# CanShark.net
KiCad netlist of a schematic drawn in EAGLE
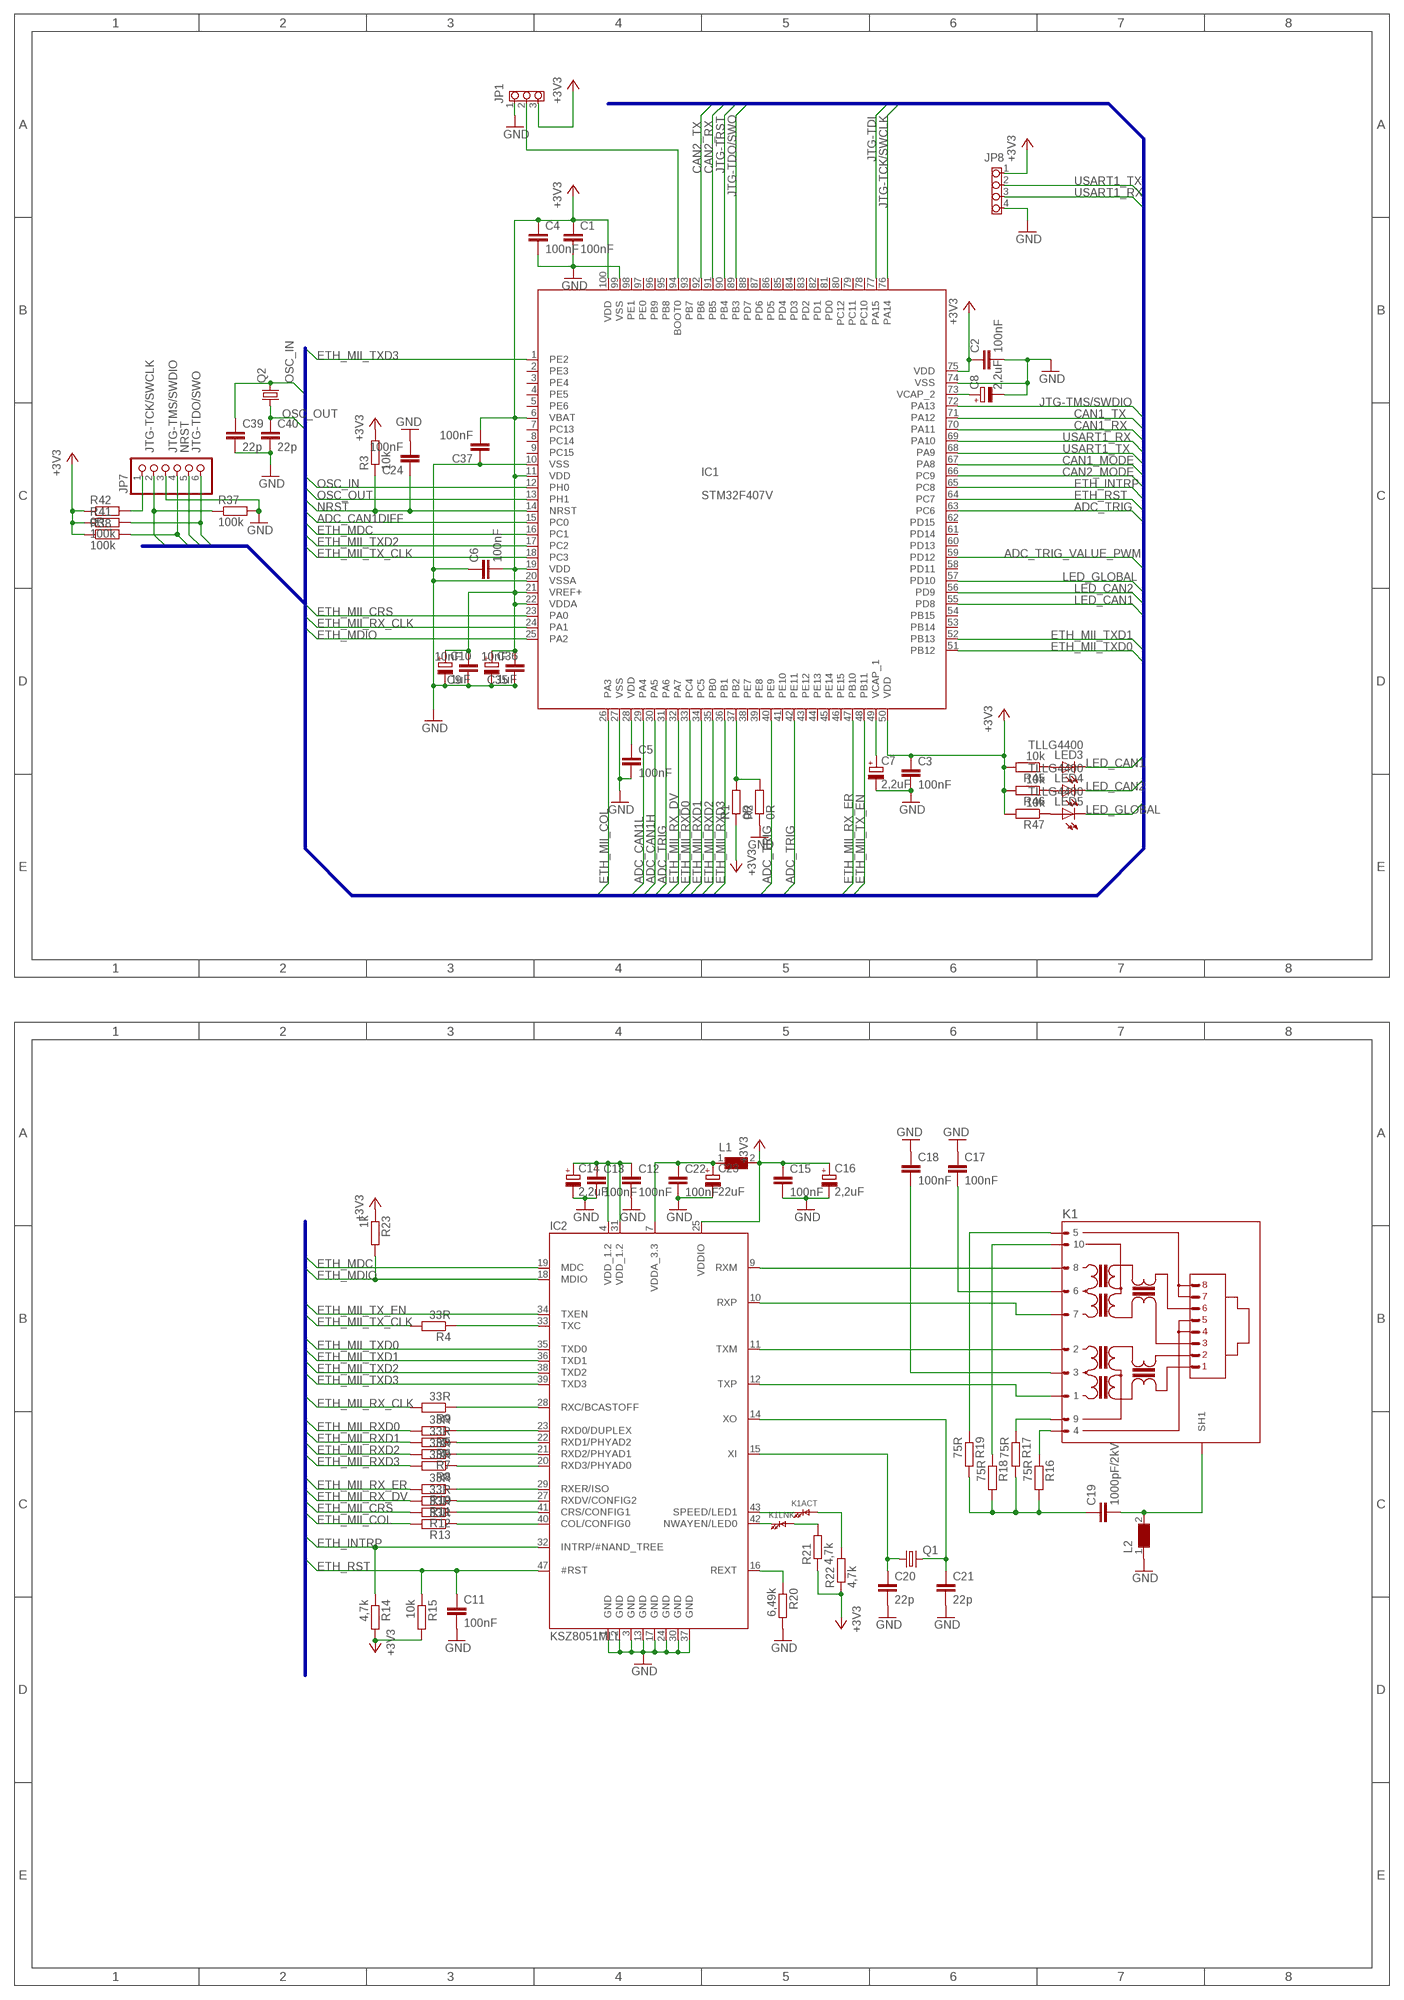
[diagram p0: schematic, sheet 1, part 1 of 3]
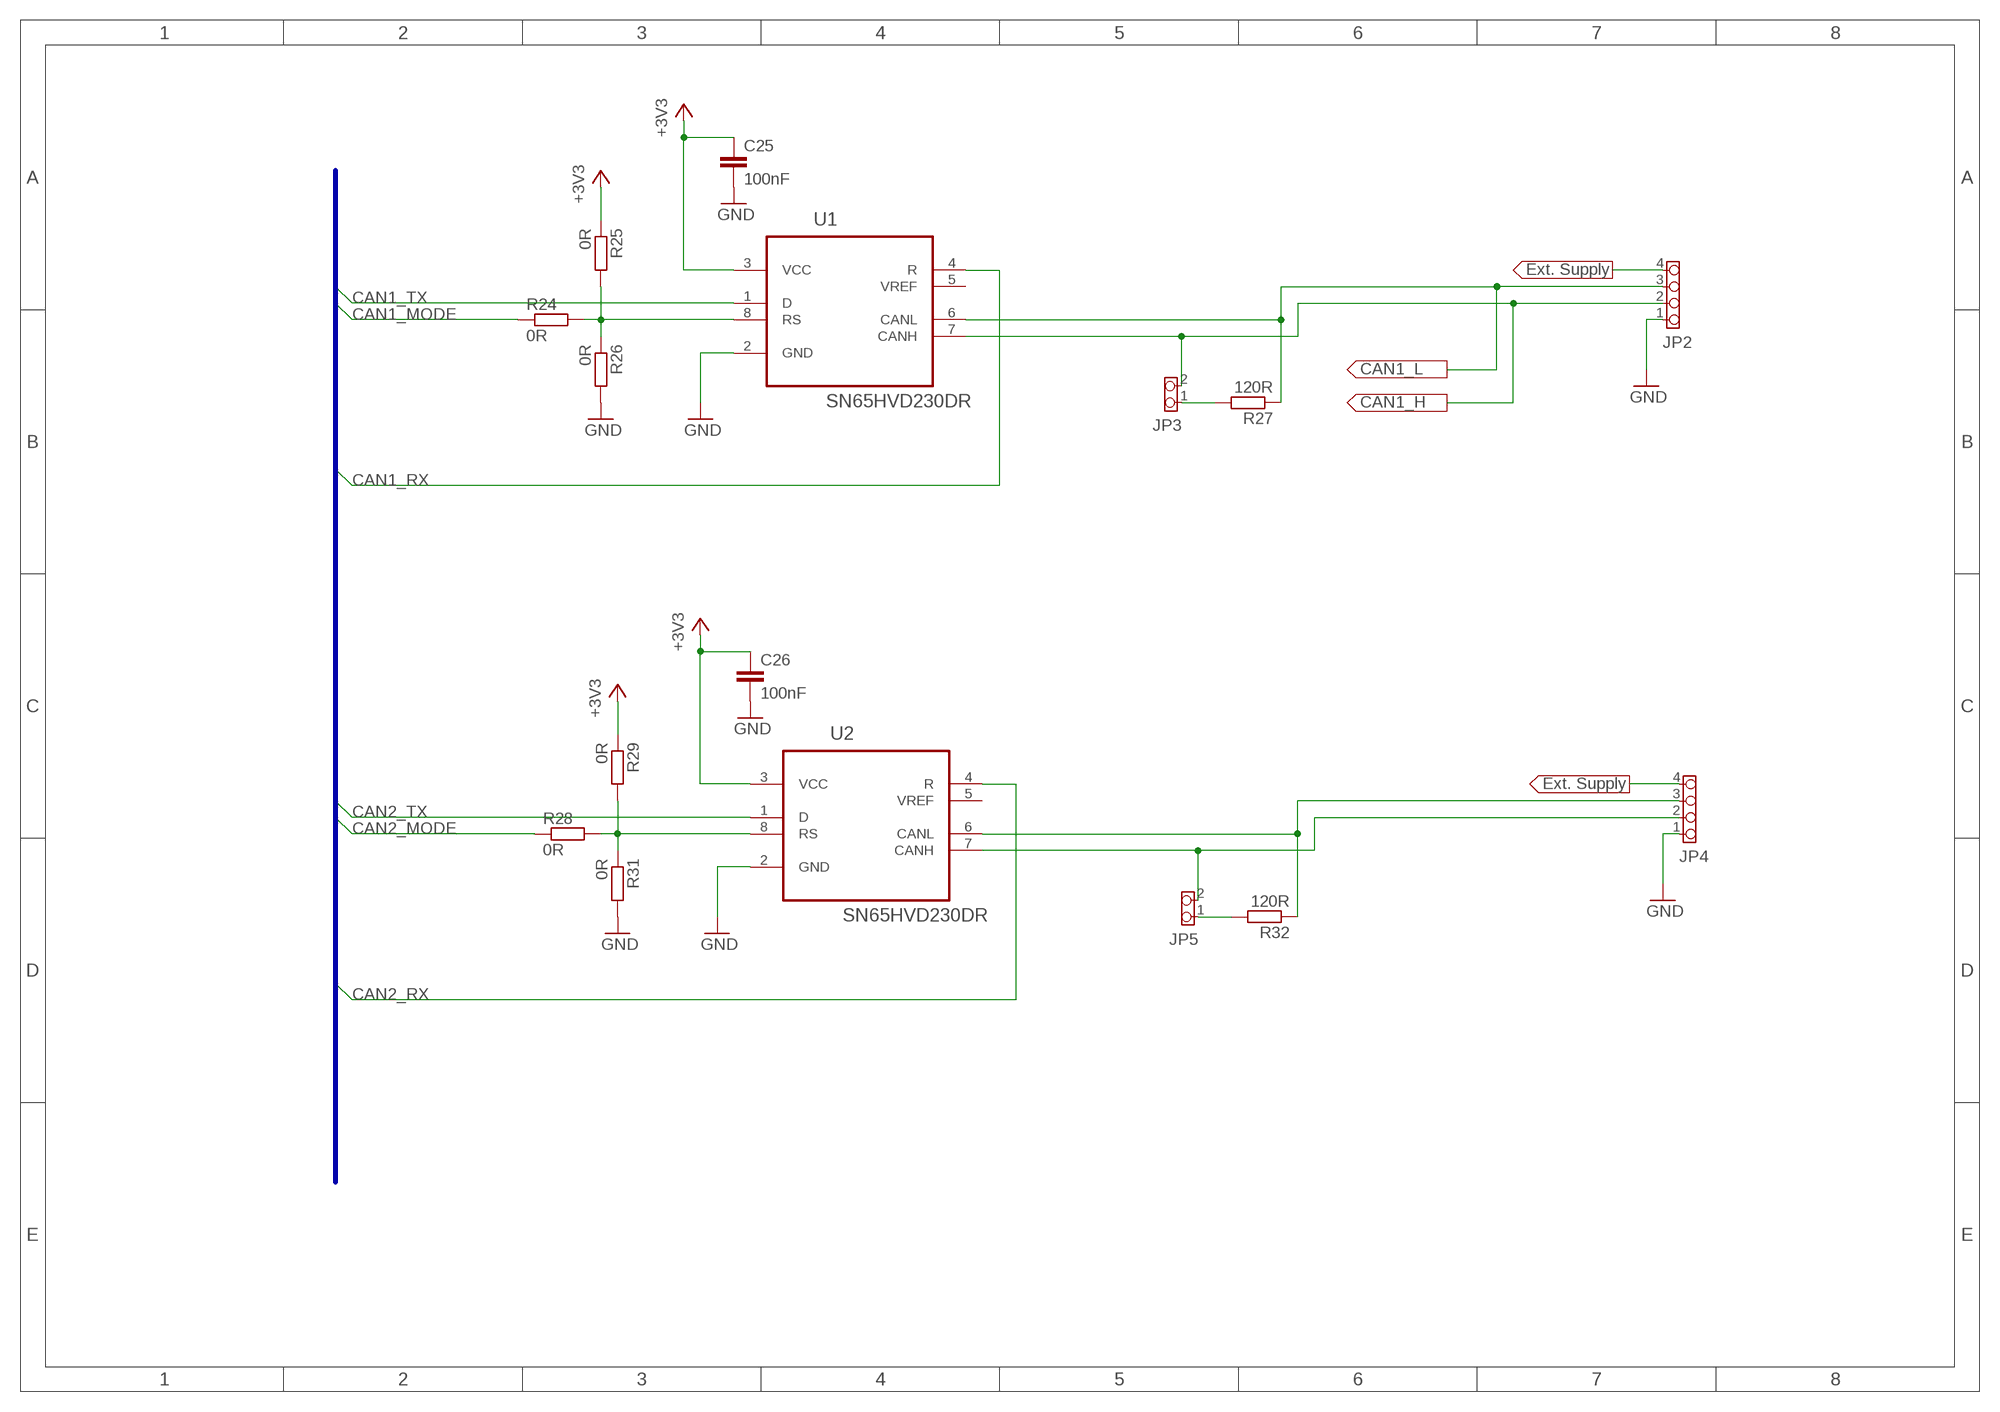
[diagram p1: schematic, sheet 1, part 2 of 3]
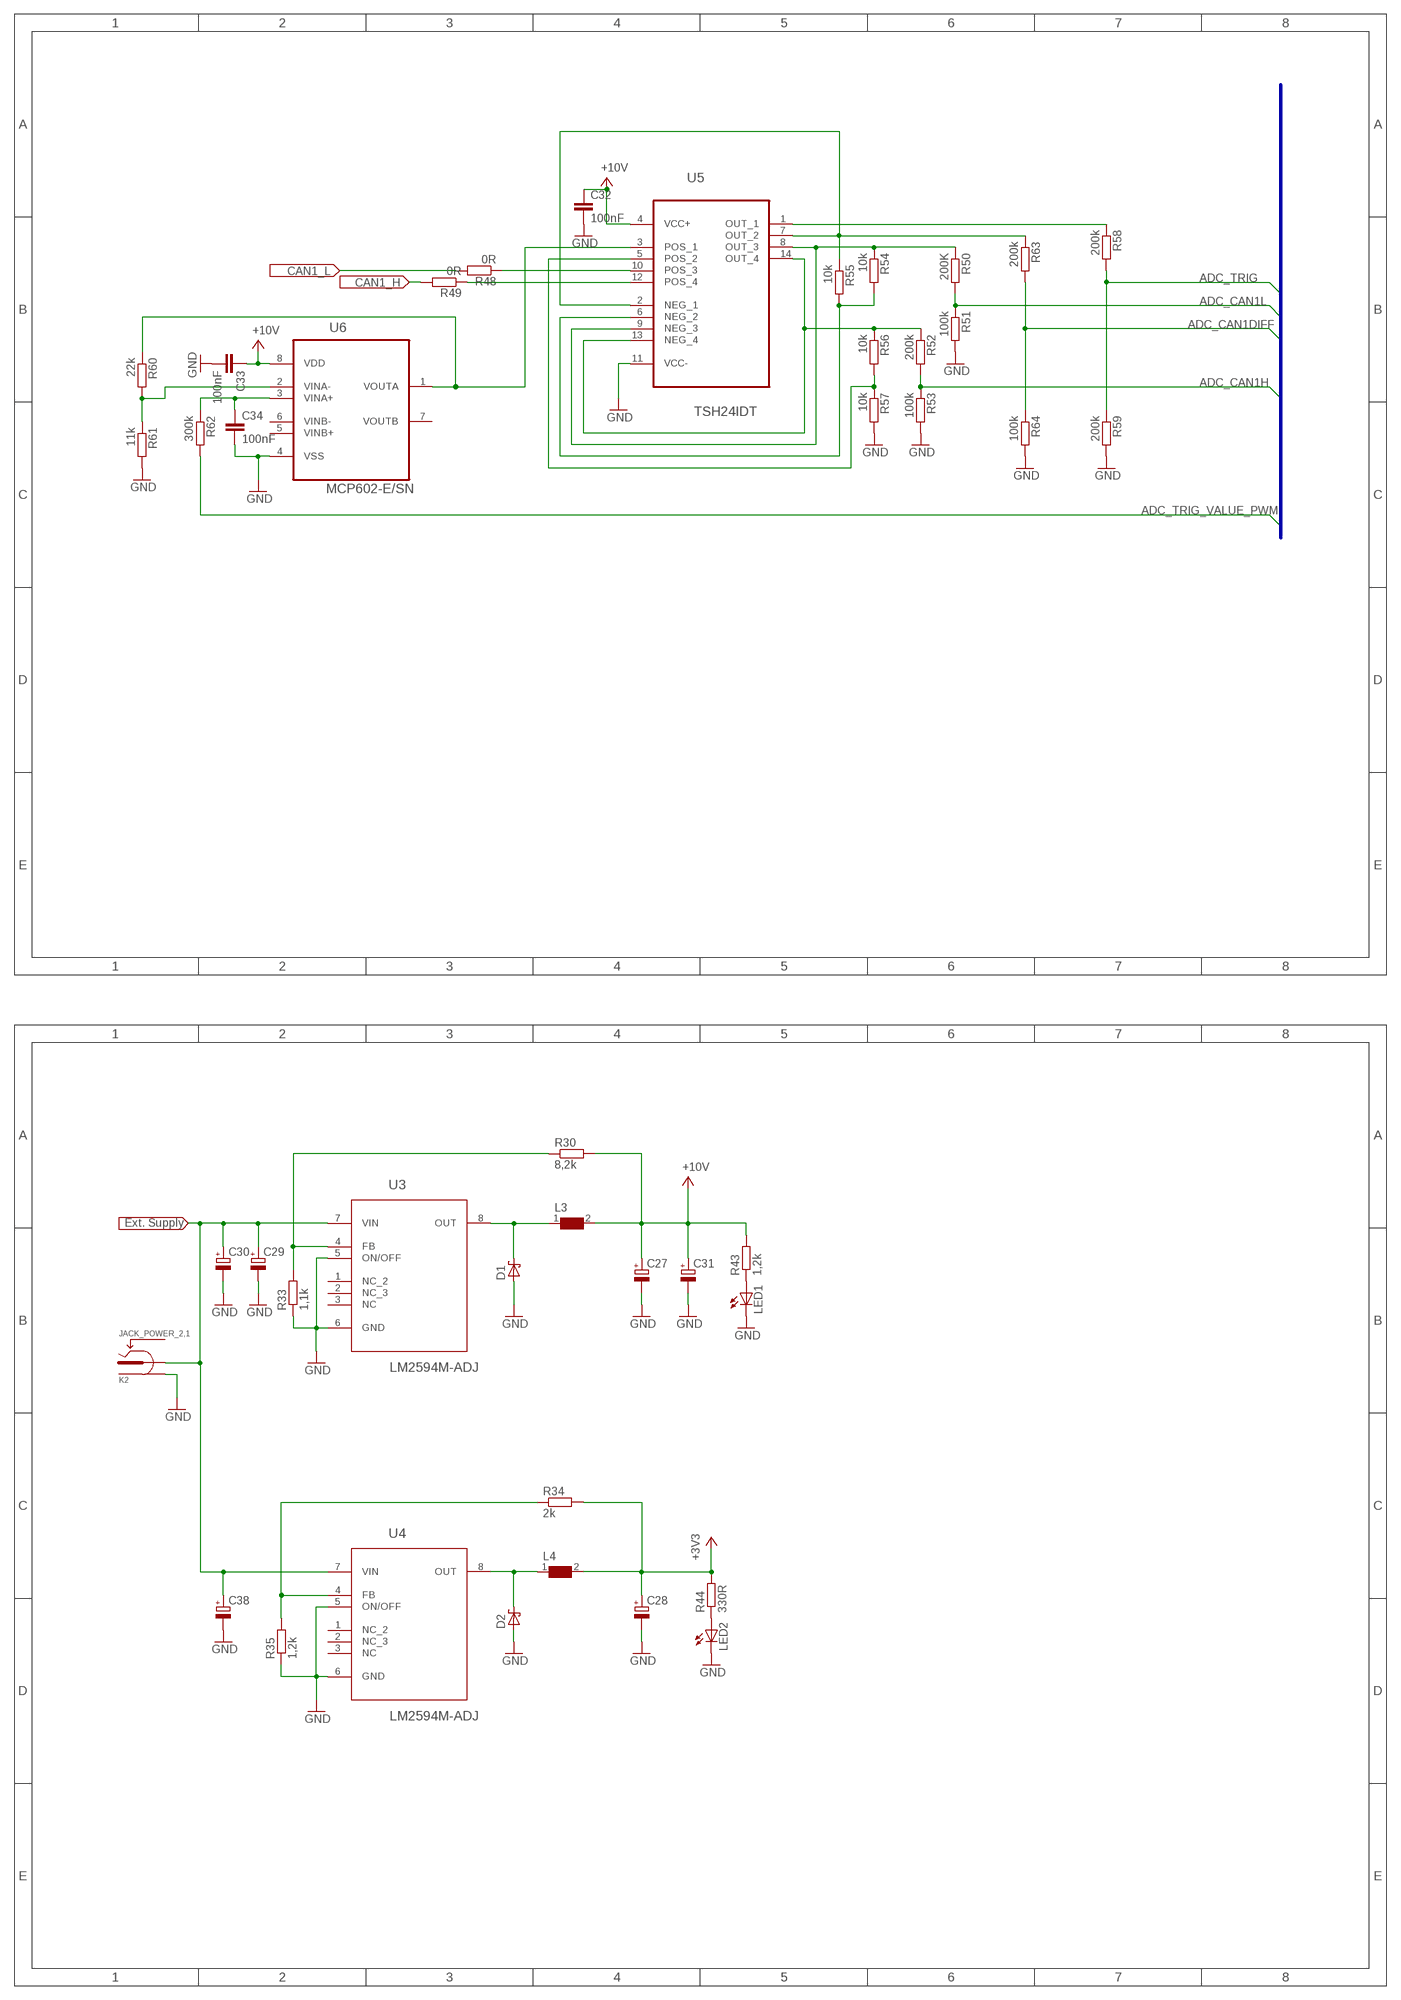
[diagram p2: schematic, sheet 1, part 3 of 3]

(export (version "E")
  (design (tool "Eeschema 10.0.6"))
  (components
    (comp (ref "C1")
      (value "100nF")
      (footprint "eagle-import:SMD0603")
      (libsource (lib "eagle-import") (part "KERAMICKYSMD0603"))
    )
    (comp (ref "C2")
      (value "100nF")
      (footprint "eagle-import:SMD0603")
      (libsource (lib "eagle-import") (part "KERAMICKYSMD0603"))
    )
    (comp (ref "C3")
      (value "100nF")
      (footprint "eagle-import:SMD0603")
      (libsource (lib "eagle-import") (part "KERAMICKYSMD0603"))
    )
    (comp (ref "C4")
      (value "100nF")
      (footprint "eagle-import:SMD0603")
      (libsource (lib "eagle-import") (part "KERAMICKYSMD0603"))
    )
    (comp (ref "C5")
      (value "100nF")
      (footprint "eagle-import:SMD0603")
      (libsource (lib "eagle-import") (part "KERAMICKYSMD0603"))
    )
    (comp (ref "C6")
      (value "100nF")
      (footprint "eagle-import:SMD0603")
      (libsource (lib "eagle-import") (part "KERAMICKYSMD0603"))
    )
    (comp (ref "C7")
      (value "2,2uF")
      (footprint "eagle-import:SMC_A")
      (libsource (lib "eagle-import") (part "CPOL-EUSMCA"))
    )
    (comp (ref "C8")
      (value "2,2uF")
      (footprint "eagle-import:SMC_A")
      (libsource (lib "eagle-import") (part "CPOL-EUSMCA"))
    )
    (comp (ref "C9")
      (value "10nF")
      (footprint "eagle-import:SMD0603")
      (libsource (lib "eagle-import") (part "KERAMICKYSMD0603"))
    )
    (comp (ref "C10")
      (value "1uF")
      (footprint "eagle-import:SMC_A")
      (libsource (lib "eagle-import") (part "CPOL-EUSMCA"))
    )
    (comp (ref "C11")
      (value "100nF")
      (footprint "eagle-import:SMD0603")
      (libsource (lib "eagle-import") (part "KERAMICKYSMD0603"))
    )
    (comp (ref "C12")
      (value "100nF")
      (footprint "eagle-import:SMD0603")
      (libsource (lib "eagle-import") (part "KERAMICKYSMD0603"))
    )
    (comp (ref "C13")
      (value "100nF")
      (footprint "eagle-import:SMD0603")
      (libsource (lib "eagle-import") (part "KERAMICKYSMD0603"))
    )
    (comp (ref "C14")
      (value "2,2uF")
      (footprint "eagle-import:SMC_A")
      (libsource (lib "eagle-import") (part "CPOL-EUSMCA"))
    )
    (comp (ref "C15")
      (value "100nF")
      (footprint "eagle-import:SMD0603")
      (libsource (lib "eagle-import") (part "KERAMICKYSMD0603"))
    )
    (comp (ref "C16")
      (value "2,2uF")
      (footprint "eagle-import:SMC_A")
      (libsource (lib "eagle-import") (part "CPOL-EUSMCA"))
    )
    (comp (ref "C17")
      (value "100nF")
      (footprint "eagle-import:SMD0603")
      (libsource (lib "eagle-import") (part "KERAMICKYSMD0603"))
    )
    (comp (ref "C18")
      (value "100nF")
      (footprint "eagle-import:SMD0603")
      (libsource (lib "eagle-import") (part "KERAMICKYSMD0603"))
    )
    (comp (ref "C19")
      (value "1000pF/2kV")
      (footprint "eagle-import:SMD1206")
      (libsource (lib "eagle-import") (part "KERAMICKYSMD1206"))
    )
    (comp (ref "C20")
      (value "22p")
      (footprint "eagle-import:SMD0603")
      (libsource (lib "eagle-import") (part "KERAMICKYSMD0603"))
    )
    (comp (ref "C21")
      (value "22p")
      (footprint "eagle-import:SMD0603")
      (libsource (lib "eagle-import") (part "KERAMICKYSMD0603"))
    )
    (comp (ref "C22")
      (value "100nF")
      (footprint "eagle-import:SMD0603")
      (libsource (lib "eagle-import") (part "KERAMICKYSMD0603"))
    )
    (comp (ref "C23")
      (value "22uF")
      (footprint "eagle-import:SMC_A")
      (libsource (lib "eagle-import") (part "CPOL-EUSMCA"))
    )
    (comp (ref "C24")
      (value "100nF")
      (footprint "eagle-import:SMD0603")
      (libsource (lib "eagle-import") (part "KERAMICKYSMD0603"))
    )
    (comp (ref "C25")
      (value "100nF")
      (footprint "eagle-import:SMD0603")
      (libsource (lib "eagle-import") (part "KERAMICKYSMD0603"))
    )
    (comp (ref "C26")
      (value "100nF")
      (footprint "eagle-import:SMD0603")
      (libsource (lib "eagle-import") (part "KERAMICKYSMD0603"))
    )
    (comp (ref "C27")
      (value "CPOL-EUC/6032-28R")
      (footprint "eagle-import:C_6032-28R")
      (libsource (lib "eagle-import") (part "CPOL-EUC/6032-28R"))
    )
    (comp (ref "C28")
      (value "CPOL-EUC/6032-28R")
      (footprint "eagle-import:C_6032-28R")
      (libsource (lib "eagle-import") (part "CPOL-EUC/6032-28R"))
    )
    (comp (ref "C29")
      (value "CPOL-EUC/6032-28R")
      (footprint "eagle-import:C_6032-28R")
      (libsource (lib "eagle-import") (part "CPOL-EUC/6032-28R"))
    )
    (comp (ref "C30")
      (value "CPOL-EUA/3216-18R")
      (footprint "eagle-import:A_3216-18R")
      (libsource (lib "eagle-import") (part "CPOL-EUA/3216-18R"))
    )
    (comp (ref "C31")
      (value "CPOL-EUA/3216-18R")
      (footprint "eagle-import:A_3216-18R")
      (libsource (lib "eagle-import") (part "CPOL-EUA/3216-18R"))
    )
    (comp (ref "C32")
      (value "100nF")
      (footprint "eagle-import:SMD0603")
      (libsource (lib "eagle-import") (part "KERAMICKYSMD0603"))
    )
    (comp (ref "C33")
      (value "100nF")
      (footprint "eagle-import:SMD0603")
      (libsource (lib "eagle-import") (part "KERAMICKYSMD0603"))
    )
    (comp (ref "C34")
      (value "100nF")
      (footprint "eagle-import:SMD0603")
      (libsource (lib "eagle-import") (part "KERAMICKYSMD0603"))
    )
    (comp (ref "C35")
      (value "10nF")
      (footprint "eagle-import:SMD0603")
      (libsource (lib "eagle-import") (part "KERAMICKYSMD0603"))
    )
    (comp (ref "C36")
      (value "1uF")
      (footprint "eagle-import:SMC_A")
      (libsource (lib "eagle-import") (part "CPOL-EUSMCA"))
    )
    (comp (ref "C37")
      (value "100nF")
      (footprint "eagle-import:SMD0603")
      (libsource (lib "eagle-import") (part "KERAMICKYSMD0603"))
    )
    (comp (ref "C38")
      (value "CPOL-EUC/6032-28R")
      (footprint "eagle-import:C_6032-28R")
      (libsource (lib "eagle-import") (part "CPOL-EUC/6032-28R"))
    )
    (comp (ref "C39")
      (value "22p")
      (footprint "eagle-import:SMD0603")
      (libsource (lib "eagle-import") (part "KERAMICKYSMD0603"))
    )
    (comp (ref "C40")
      (value "22p")
      (footprint "eagle-import:SMD0603")
      (libsource (lib "eagle-import") (part "KERAMICKYSMD0603"))
    )
    (comp (ref "D1")
      (value "SCHOTTKY-DIODESMD")
      (footprint "eagle-import:SMB")
      (libsource (lib "eagle-import") (part "SCHOTTKY-DIODESMD"))
    )
    (comp (ref "D2")
      (value "SCHOTTKY-DIODESMD")
      (footprint "eagle-import:SMB")
      (libsource (lib "eagle-import") (part "SCHOTTKY-DIODESMD"))
    )
    (comp (ref "IC1")
      (value "STM32F407V")
      (footprint "eagle-import:LQFP100")
      (libsource (lib "eagle-import") (part "STM32F4V07"))
    )
    (comp (ref "IC2")
      (value "KSZ8051MLL")
      (footprint "eagle-import:LQFP48")
      (libsource (lib "eagle-import") (part "KSZ8051MLL"))
    )
    (comp (ref "JP1")
      (value "PINHD-1X3")
      (footprint "eagle-import:1X03_254")
      (libsource (lib "eagle-import") (part "PINHD-1X3"))
    )
    (comp (ref "JP2")
      (value "PINHD-1X4_508_H")
      (footprint "eagle-import:1X04_508_H")
      (libsource (lib "eagle-import") (part "PINHD-1X4_508_H"))
    )
    (comp (ref "JP3")
      (value "PINHD-1X2")
      (footprint "eagle-import:1X02_254")
      (libsource (lib "eagle-import") (part "PINHD-1X2"))
    )
    (comp (ref "JP4")
      (value "PINHD-1X4_508_H")
      (footprint "eagle-import:1X04_508_H")
      (libsource (lib "eagle-import") (part "PINHD-1X4_508_H"))
    )
    (comp (ref "JP5")
      (value "PINHD-1X2")
      (footprint "eagle-import:1X02_254")
      (libsource (lib "eagle-import") (part "PINHD-1X2"))
    )
    (comp (ref "JP7")
      (value "PINHD-1X6")
      (footprint "eagle-import:1X06")
      (libsource (lib "eagle-import") (part "PINHD-1X6"))
    )
    (comp (ref "JP8")
      (value "PINHD-1X4")
      (footprint "eagle-import:1X04_254")
      (libsource (lib "eagle-import") (part "PINHD-1X4"))
    )
    (comp (ref "K1")
      (value "RJ45_TRAFO")
      (footprint "eagle-import:RJ45_TRAFO")
      (libsource (lib "eagle-import") (part "RJ45_TRAFO"))
    )
    (comp (ref "K2")
      (value "JACK_POWER_2,1")
      (footprint "eagle-import:J_P_2,1")
      (libsource (lib "eagle-import") (part "JACK_POWER_?2,1"))
    )
    (comp (ref "L1")
      (value "WE-CBF_HF-742863122_0603")
      (footprint "eagle-import:0603")
      (fields (field (name "MPN") "742863122"))
      (libsource (lib "eagle-import") (part "WE-CBF_HF_0603-742863122"))
    )
    (comp (ref "L2")
      (value "WE-CBF_HF-742863122_0603")
      (footprint "eagle-import:0603")
      (fields (field (name "MPN") "742863122"))
      (libsource (lib "eagle-import") (part "WE-CBF_HF_0603-742863122"))
    )
    (comp (ref "L3")
      (value "WE-TPC-744066180_1028/1038")
      (footprint "eagle-import:WE-TPC_1028_1038")
      (fields (field (name "MPN") "744066180"))
      (libsource (lib "eagle-import") (part "WE-TPC_1028/1038-744066180"))
    )
    (comp (ref "L4")
      (value "WE-TPC-744066180_1028/1038")
      (footprint "eagle-import:WE-TPC_1028_1038")
      (fields (field (name "MPN") "744066180"))
      (libsource (lib "eagle-import") (part "WE-TPC_1028/1038-744066180"))
    )
    (comp (ref "LED1")
      (value "LEDSML0603")
      (footprint "eagle-import:SML0603")
      (libsource (lib "eagle-import") (part "LEDSML0603"))
    )
    (comp (ref "LED2")
      (value "LEDSML0603")
      (footprint "eagle-import:SML0603")
      (libsource (lib "eagle-import") (part "LEDSML0603"))
    )
    (comp (ref "LED3")
      (value "TLLG4400")
      (footprint "eagle-import:LED3MM")
      (fields (field (name "MF") "VISHAY SEMICONDUCTOR"))
      (libsource (lib "eagle-import") (part "TLLG4400"))
    )
    (comp (ref "LED4")
      (value "TLLG4400")
      (footprint "eagle-import:LED3MM")
      (fields (field (name "MF") "VISHAY SEMICONDUCTOR"))
      (libsource (lib "eagle-import") (part "TLLG4400"))
    )
    (comp (ref "LED5")
      (value "TLLG4400")
      (footprint "eagle-import:LED3MM")
      (fields (field (name "MF") "VISHAY SEMICONDUCTOR"))
      (libsource (lib "eagle-import") (part "TLLG4400"))
    )
    (comp (ref "Q1")
      (value "CRYSTALHC49U-V")
      (footprint "eagle-import:HC49U-V")
      (libsource (lib "eagle-import") (part "CRYSTALHC49U-V"))
    )
    (comp (ref "Q2")
      (value "CRYSTALHC49U-V")
      (footprint "eagle-import:HC49U-V")
      (libsource (lib "eagle-import") (part "CRYSTALHC49U-V"))
    )
    (comp (ref "R1")
      (value "0R")
      (footprint "eagle-import:R0603")
      (libsource (lib "eagle-import") (part "R-EU_R0603"))
    )
    (comp (ref "R2")
      (value "0R")
      (footprint "eagle-import:R0603")
      (libsource (lib "eagle-import") (part "R-EU_R0603"))
    )
    (comp (ref "R3")
      (value "10k")
      (footprint "eagle-import:R0603")
      (libsource (lib "eagle-import") (part "R-EU_R0603"))
    )
    (comp (ref "R4")
      (value "33R")
      (footprint "eagle-import:R0603")
      (libsource (lib "eagle-import") (part "R-EU_R0603"))
    )
    (comp (ref "R5")
      (value "33R")
      (footprint "eagle-import:R0603")
      (libsource (lib "eagle-import") (part "R-EU_R0603"))
    )
    (comp (ref "R6")
      (value "33R")
      (footprint "eagle-import:R0603")
      (libsource (lib "eagle-import") (part "R-EU_R0603"))
    )
    (comp (ref "R7")
      (value "33R")
      (footprint "eagle-import:R0603")
      (libsource (lib "eagle-import") (part "R-EU_R0603"))
    )
    (comp (ref "R8")
      (value "33R")
      (footprint "eagle-import:R0603")
      (libsource (lib "eagle-import") (part "R-EU_R0603"))
    )
    (comp (ref "R9")
      (value "33R")
      (footprint "eagle-import:R0603")
      (libsource (lib "eagle-import") (part "R-EU_R0603"))
    )
    (comp (ref "R10")
      (value "33R")
      (footprint "eagle-import:R0603")
      (libsource (lib "eagle-import") (part "R-EU_R0603"))
    )
    (comp (ref "R11")
      (value "33R")
      (footprint "eagle-import:R0603")
      (libsource (lib "eagle-import") (part "R-EU_R0603"))
    )
    (comp (ref "R12")
      (value "33R")
      (footprint "eagle-import:R0603")
      (libsource (lib "eagle-import") (part "R-EU_R0603"))
    )
    (comp (ref "R13")
      (value "33R")
      (footprint "eagle-import:R0603")
      (libsource (lib "eagle-import") (part "R-EU_R0603"))
    )
    (comp (ref "R14")
      (value "4,7k")
      (footprint "eagle-import:R0603")
      (libsource (lib "eagle-import") (part "R-EU_R0603"))
    )
    (comp (ref "R15")
      (value "10k")
      (footprint "eagle-import:R0603")
      (libsource (lib "eagle-import") (part "R-EU_R0603"))
    )
    (comp (ref "R16")
      (value "75R")
      (footprint "eagle-import:R0603")
      (libsource (lib "eagle-import") (part "R-EU_R0603"))
    )
    (comp (ref "R17")
      (value "75R")
      (footprint "eagle-import:R0603")
      (libsource (lib "eagle-import") (part "R-EU_R0603"))
    )
    (comp (ref "R18")
      (value "75R")
      (footprint "eagle-import:R0603")
      (libsource (lib "eagle-import") (part "R-EU_R0603"))
    )
    (comp (ref "R19")
      (value "75R")
      (footprint "eagle-import:R0603")
      (libsource (lib "eagle-import") (part "R-EU_R0603"))
    )
    (comp (ref "R20")
      (value "6,49k")
      (footprint "eagle-import:R0603")
      (libsource (lib "eagle-import") (part "R-EU_R0603"))
    )
    (comp (ref "R21")
      (value "4,7k")
      (footprint "eagle-import:R0603")
      (libsource (lib "eagle-import") (part "R-EU_R0603"))
    )
    (comp (ref "R22")
      (value "4,7k")
      (footprint "eagle-import:R0603")
      (libsource (lib "eagle-import") (part "R-EU_R0603"))
    )
    (comp (ref "R23")
      (value "1k")
      (footprint "eagle-import:R0603")
      (libsource (lib "eagle-import") (part "R-EU_R0603"))
    )
    (comp (ref "R24")
      (value "0R")
      (footprint "eagle-import:R0603")
      (libsource (lib "eagle-import") (part "R-EU_R0603"))
    )
    (comp (ref "R25")
      (value "0R")
      (footprint "eagle-import:R0603")
      (libsource (lib "eagle-import") (part "R-EU_R0603"))
    )
    (comp (ref "R26")
      (value "0R")
      (footprint "eagle-import:R0603")
      (libsource (lib "eagle-import") (part "R-EU_R0603"))
    )
    (comp (ref "R27")
      (value "120R")
      (footprint "eagle-import:R0603")
      (libsource (lib "eagle-import") (part "R-EU_R0603"))
    )
    (comp (ref "R28")
      (value "0R")
      (footprint "eagle-import:R0603")
      (libsource (lib "eagle-import") (part "R-EU_R0603"))
    )
    (comp (ref "R29")
      (value "0R")
      (footprint "eagle-import:R0603")
      (libsource (lib "eagle-import") (part "R-EU_R0603"))
    )
    (comp (ref "R30")
      (value "8,2k")
      (footprint "eagle-import:R0603")
      (libsource (lib "eagle-import") (part "R-EU_R0603"))
    )
    (comp (ref "R31")
      (value "0R")
      (footprint "eagle-import:R0603")
      (libsource (lib "eagle-import") (part "R-EU_R0603"))
    )
    (comp (ref "R32")
      (value "120R")
      (footprint "eagle-import:R0603")
      (libsource (lib "eagle-import") (part "R-EU_R0603"))
    )
    (comp (ref "R33")
      (value "1,1k")
      (footprint "eagle-import:R0603")
      (libsource (lib "eagle-import") (part "R-EU_R0603"))
    )
    (comp (ref "R34")
      (value "2k")
      (footprint "eagle-import:R0603")
      (libsource (lib "eagle-import") (part "R-EU_R0603"))
    )
    (comp (ref "R35")
      (value "1,2k")
      (footprint "eagle-import:R0603")
      (libsource (lib "eagle-import") (part "R-EU_R0603"))
    )
    (comp (ref "R37")
      (value "100k")
      (footprint "eagle-import:R0603")
      (libsource (lib "eagle-import") (part "R-EU_R0603"))
    )
    (comp (ref "R38")
      (value "100k")
      (footprint "eagle-import:R0603")
      (libsource (lib "eagle-import") (part "R-EU_R0603"))
    )
    (comp (ref "R41")
      (value "100k")
      (footprint "eagle-import:R0603")
      (libsource (lib "eagle-import") (part "R-EU_R0603"))
    )
    (comp (ref "R42")
      (value "0R")
      (footprint "eagle-import:R0603")
      (libsource (lib "eagle-import") (part "R-EU_R0603"))
    )
    (comp (ref "R43")
      (value "1,2k")
      (footprint "eagle-import:R0603")
      (libsource (lib "eagle-import") (part "R-EU_R0603"))
    )
    (comp (ref "R44")
      (value "330R")
      (footprint "eagle-import:R0603")
      (libsource (lib "eagle-import") (part "R-EU_R0603"))
    )
    (comp (ref "R45")
      (value "10k")
      (footprint "eagle-import:R0603")
      (libsource (lib "eagle-import") (part "R-EU_R0603"))
    )
    (comp (ref "R46")
      (value "10k")
      (footprint "eagle-import:R0603")
      (libsource (lib "eagle-import") (part "R-EU_R0603"))
    )
    (comp (ref "R47")
      (value "10k")
      (footprint "eagle-import:R0603")
      (libsource (lib "eagle-import") (part "R-EU_R0603"))
    )
    (comp (ref "R48")
      (value "0R")
      (footprint "eagle-import:R0603")
      (libsource (lib "eagle-import") (part "R-EU_R0603"))
    )
    (comp (ref "R49")
      (value "0R")
      (footprint "eagle-import:R0603")
      (libsource (lib "eagle-import") (part "R-EU_R0603"))
    )
    (comp (ref "R50")
      (value "200K")
      (footprint "eagle-import:R0603")
      (libsource (lib "eagle-import") (part "R-EU_R0603"))
    )
    (comp (ref "R51")
      (value "100k")
      (footprint "eagle-import:R0603")
      (libsource (lib "eagle-import") (part "R-EU_R0603"))
    )
    (comp (ref "R52")
      (value "200k")
      (footprint "eagle-import:R0603")
      (libsource (lib "eagle-import") (part "R-EU_R0603"))
    )
    (comp (ref "R53")
      (value "100k")
      (footprint "eagle-import:R0603")
      (libsource (lib "eagle-import") (part "R-EU_R0603"))
    )
    (comp (ref "R54")
      (value "10k")
      (footprint "eagle-import:R0603")
      (libsource (lib "eagle-import") (part "R-EU_R0603"))
    )
    (comp (ref "R55")
      (value "10k")
      (footprint "eagle-import:R0603")
      (libsource (lib "eagle-import") (part "R-EU_R0603"))
    )
    (comp (ref "R56")
      (value "10k")
      (footprint "eagle-import:R0603")
      (libsource (lib "eagle-import") (part "R-EU_R0603"))
    )
    (comp (ref "R57")
      (value "10k")
      (footprint "eagle-import:R0603")
      (libsource (lib "eagle-import") (part "R-EU_R0603"))
    )
    (comp (ref "R58")
      (value "200k")
      (footprint "eagle-import:R0603")
      (libsource (lib "eagle-import") (part "R-EU_R0603"))
    )
    (comp (ref "R59")
      (value "200k")
      (footprint "eagle-import:R0603")
      (libsource (lib "eagle-import") (part "R-EU_R0603"))
    )
    (comp (ref "R60")
      (value "22k")
      (footprint "eagle-import:R0603")
      (libsource (lib "eagle-import") (part "R-EU_R0603"))
    )
    (comp (ref "R61")
      (value "11k")
      (footprint "eagle-import:R0603")
      (libsource (lib "eagle-import") (part "R-EU_R0603"))
    )
    (comp (ref "R62")
      (value "300k")
      (footprint "eagle-import:R0603")
      (libsource (lib "eagle-import") (part "R-EU_R0603"))
    )
    (comp (ref "R63")
      (value "200k")
      (footprint "eagle-import:R0603")
      (libsource (lib "eagle-import") (part "R-EU_R0603"))
    )
    (comp (ref "R64")
      (value "100k")
      (footprint "eagle-import:R0603")
      (libsource (lib "eagle-import") (part "R-EU_R0603"))
    )
    (comp (ref "U1")
      (value "SN65HVD230DR")
      (footprint "eagle-import:SOIC127P600X175-8N")
      (libsource (lib "eagle-import") (part "SN65HVD230DR"))
    )
    (comp (ref "U2")
      (value "SN65HVD230DR")
      (footprint "eagle-import:SOIC127P600X175-8N")
      (libsource (lib "eagle-import") (part "SN65HVD230DR"))
    )
    (comp (ref "U3")
      (value "LM2594M-ADJ")
      (footprint "eagle-import:SOIC127P620X175-8N")
      (libsource (lib "eagle-import") (part "LM2594M-ADJ"))
    )
    (comp (ref "U4")
      (value "LM2594M-ADJ")
      (footprint "eagle-import:SOIC127P620X175-8N")
      (libsource (lib "eagle-import") (part "LM2594M-ADJ"))
    )
    (comp (ref "U5")
      (value "TSH24IDT")
      (footprint "eagle-import:SOIC127P600X175-14N")
      (libsource (lib "eagle-import") (part "TSH24IDT"))
    )
    (comp (ref "U6")
      (value "MCP602-E/SN")
      (footprint "eagle-import:SOIC127P600X175-8N")
      (libsource (lib "eagle-import") (part "MCP602-E/SN"))
    )
  )
  (nets
    (net (code "1") (name "+3V3") (class "Default")
      (node (ref "C1") (pin "1") (pinfunction "1_1") (pintype "passive"))
      (node (ref "C10") (pin "+") (pinfunction "+_+") (pintype "passive"))
      (node (ref "C15") (pin "1") (pinfunction "1_1") (pintype "passive"))
      (node (ref "C16") (pin "+") (pinfunction "+_+") (pintype "passive"))
      (node (ref "C2") (pin "1") (pinfunction "1_1") (pintype "passive"))
      (node (ref "C25") (pin "1") (pinfunction "1_1") (pintype "passive"))
      (node (ref "C26") (pin "1") (pinfunction "1_1") (pintype "passive"))
      (node (ref "C28") (pin "+") (pinfunction "+_+") (pintype "passive"))
      (node (ref "C3") (pin "1") (pinfunction "1_1") (pintype "passive"))
      (node (ref "C35") (pin "2") (pinfunction "2_2") (pintype "passive"))
      (node (ref "C36") (pin "+") (pinfunction "+_+") (pintype "passive"))
      (node (ref "C37") (pin "2") (pinfunction "2_2") (pintype "passive"))
      (node (ref "C4") (pin "1") (pinfunction "1_1") (pintype "passive"))
      (node (ref "C6") (pin "2") (pinfunction "2_2") (pintype "passive"))
      (node (ref "C9") (pin "2") (pinfunction "2_2") (pintype "passive"))
      (node (ref "IC1") (pin "100") (pinfunction "VDD_100") (pintype "passive"))
      (node (ref "IC1") (pin "11") (pinfunction "VDD_11") (pintype "passive"))
      (node (ref "IC1") (pin "19") (pinfunction "VDD_19") (pintype "passive"))
      (node (ref "IC1") (pin "21") (pinfunction "VREF+_21") (pintype "passive"))
      (node (ref "IC1") (pin "22") (pinfunction "VDDA_22") (pintype "passive"))
      (node (ref "IC1") (pin "50") (pinfunction "VDD_50") (pintype "passive"))
      (node (ref "IC1") (pin "6") (pinfunction "VBAT_6") (pintype "passive"))
      (node (ref "IC1") (pin "75") (pinfunction "VDD_75") (pintype "passive"))
      (node (ref "IC2") (pin "25") (pinfunction "VDDIO_25") (pintype "passive"))
      (node (ref "JP1") (pin "3") (pinfunction "3_3") (pintype "passive"))
      (node (ref "JP8") (pin "1") (pinfunction "1_1") (pintype "passive"))
      (node (ref "L1") (pin "2") (pinfunction "2_2") (pintype "passive"))
      (node (ref "L4") (pin "2") (pinfunction "2_2") (pintype "passive"))
      (node (ref "R1") (pin "1") (pinfunction "1_1") (pintype "passive"))
      (node (ref "R14") (pin "2") (pinfunction "2_2") (pintype "passive"))
      (node (ref "R15") (pin "2") (pinfunction "2_2") (pintype "passive"))
      (node (ref "R21") (pin "1") (pinfunction "1_1") (pintype "passive"))
      (node (ref "R22") (pin "1") (pinfunction "1_1") (pintype "passive"))
      (node (ref "R23") (pin "1") (pinfunction "1_1") (pintype "passive"))
      (node (ref "R25") (pin "1") (pinfunction "1_1") (pintype "passive"))
      (node (ref "R29") (pin "1") (pinfunction "1_1") (pintype "passive"))
      (node (ref "R3") (pin "2") (pinfunction "2_2") (pintype "passive"))
      (node (ref "R34") (pin "2") (pinfunction "2_2") (pintype "passive"))
      (node (ref "R38") (pin "1") (pinfunction "1_1") (pintype "passive"))
      (node (ref "R41") (pin "1") (pinfunction "1_1") (pintype "passive"))
      (node (ref "R42") (pin "1") (pinfunction "1_1") (pintype "passive"))
      (node (ref "R44") (pin "2") (pinfunction "2_2") (pintype "passive"))
      (node (ref "R45") (pin "2") (pinfunction "2_2") (pintype "passive"))
      (node (ref "R46") (pin "2") (pinfunction "2_2") (pintype "passive"))
      (node (ref "R47") (pin "2") (pinfunction "2_2") (pintype "passive"))
      (node (ref "U1") (pin "3") (pinfunction "VCC_3") (pintype "power_in"))
      (node (ref "U2") (pin "3") (pinfunction "VCC_3") (pintype "power_in"))
    )
    (net (code "3") (name "ADC_CAN1DIFF") (class "Default")
      (node (ref "IC1") (pin "15") (pinfunction "PC0_15") (pintype "passive"))
      (node (ref "R63") (pin "2") (pinfunction "2_2") (pintype "passive"))
      (node (ref "R64") (pin "1") (pinfunction "1_1") (pintype "passive"))
    )
    (net (code "4") (name "ADC_CAN1H") (class "Default")
      (node (ref "IC1") (pin "30") (pinfunction "PA5_30") (pintype "passive"))
      (node (ref "R52") (pin "2") (pinfunction "2_2") (pintype "passive"))
      (node (ref "R53") (pin "1") (pinfunction "1_1") (pintype "passive"))
    )
    (net (code "5") (name "ADC_CAN1L") (class "Default")
      (node (ref "IC1") (pin "29") (pinfunction "PA4_29") (pintype "passive"))
      (node (ref "R50") (pin "2") (pinfunction "2_2") (pintype "passive"))
      (node (ref "R51") (pin "1") (pinfunction "1_1") (pintype "passive"))
    )
    (net (code "6") (name "ADC_TRIG") (class "Default")
      (node (ref "IC1") (pin "31") (pinfunction "PA6_31") (pintype "passive"))
      (node (ref "IC1") (pin "40") (pinfunction "PE9_40") (pintype "passive"))
      (node (ref "IC1") (pin "42") (pinfunction "PE11_42") (pintype "passive"))
      (node (ref "IC1") (pin "63") (pinfunction "PC6_63") (pintype "passive"))
      (node (ref "R58") (pin "2") (pinfunction "2_2") (pintype "passive"))
      (node (ref "R59") (pin "1") (pinfunction "1_1") (pintype "passive"))
    )
    (net (code "7") (name "ADC_TRIG_VALUE_PWM") (class "Default")
      (node (ref "IC1") (pin "59") (pinfunction "PD12_59") (pintype "passive"))
      (node (ref "R62") (pin "2") (pinfunction "2_2") (pintype "passive"))
    )
    (net (code "8") (name "CAN1_H") (class "Default")
      (node (ref "JP2") (pin "2") (pinfunction "2_2") (pintype "passive"))
      (node (ref "JP3") (pin "2") (pinfunction "2_2") (pintype "passive"))
      (node (ref "R49") (pin "2") (pinfunction "2_2") (pintype "passive"))
      (node (ref "U1") (pin "7") (pinfunction "CANH_7") (pintype "output"))
    )
    (net (code "9") (name "CAN1_L") (class "Default")
      (node (ref "JP2") (pin "3") (pinfunction "3_3") (pintype "passive"))
      (node (ref "R27") (pin "1") (pinfunction "1_1") (pintype "passive"))
      (node (ref "R48") (pin "2") (pinfunction "2_2") (pintype "passive"))
      (node (ref "U1") (pin "6") (pinfunction "CANL_6") (pintype "output"))
    )
    (net (code "10") (name "CAN1_MODE") (class "Default")
      (node (ref "IC1") (pin "67") (pinfunction "PA8_67") (pintype "passive"))
      (node (ref "R24") (pin "1") (pinfunction "1_1") (pintype "passive"))
    )
    (net (code "11") (name "CAN1_RX") (class "Default")
      (node (ref "IC1") (pin "70") (pinfunction "PA11_70") (pintype "passive"))
      (node (ref "U1") (pin "4") (pinfunction "R_4") (pintype "output"))
    )
    (net (code "12") (name "CAN1_TX") (class "Default")
      (node (ref "IC1") (pin "71") (pinfunction "PA12_71") (pintype "passive"))
      (node (ref "U1") (pin "1") (pinfunction "D_1") (pintype "input"))
    )
    (net (code "13") (name "CAN2_MODE") (class "Default")
      (node (ref "IC1") (pin "66") (pinfunction "PC9_66") (pintype "passive"))
      (node (ref "R28") (pin "1") (pinfunction "1_1") (pintype "passive"))
    )
    (net (code "14") (name "CAN2_RX") (class "Default")
      (node (ref "IC1") (pin "91") (pinfunction "PB5_91") (pintype "passive"))
      (node (ref "U2") (pin "4") (pinfunction "R_4") (pintype "output"))
    )
    (net (code "15") (name "CAN2_TX") (class "Default")
      (node (ref "IC1") (pin "92") (pinfunction "PB6_92") (pintype "passive"))
      (node (ref "U2") (pin "1") (pinfunction "D_1") (pintype "input"))
    )
    (net (code "16") (name "ETH_INTRP") (class "Default")
      (node (ref "IC1") (pin "65") (pinfunction "PC8_65") (pintype "passive"))
      (node (ref "IC2") (pin "32") (pinfunction "INTRP/#NAND_TREE_32") (pintype "passive"))
      (node (ref "R14") (pin "1") (pinfunction "1_1") (pintype "passive"))
    )
    (net (code "17") (name "ETH_MDC") (class "Default")
      (node (ref "IC1") (pin "16") (pinfunction "PC1_16") (pintype "passive"))
      (node (ref "IC2") (pin "19") (pinfunction "MDC_19") (pintype "passive"))
    )
    (net (code "18") (name "ETH_MDIO") (class "Default")
      (node (ref "IC1") (pin "25") (pinfunction "PA2_25") (pintype "passive"))
      (node (ref "IC2") (pin "18") (pinfunction "MDIO_18") (pintype "passive"))
      (node (ref "R23") (pin "2") (pinfunction "2_2") (pintype "passive"))
    )
    (net (code "19") (name "ETH_MII_COL") (class "Default")
      (node (ref "IC1") (pin "26") (pinfunction "PA3_26") (pintype "passive"))
      (node (ref "R13") (pin "2") (pinfunction "2_2") (pintype "passive"))
    )
    (net (code "20") (name "ETH_MII_CRS") (class "Default")
      (node (ref "IC1") (pin "23") (pinfunction "PA0_23") (pintype "passive"))
      (node (ref "R12") (pin "2") (pinfunction "2_2") (pintype "passive"))
    )
    (net (code "21") (name "ETH_MII_RXD0") (class "Default")
      (node (ref "IC1") (pin "33") (pinfunction "PC4_33") (pintype "passive"))
      (node (ref "R5") (pin "2") (pinfunction "2_2") (pintype "passive"))
    )
    (net (code "22") (name "ETH_MII_RXD1") (class "Default")
      (node (ref "IC1") (pin "34") (pinfunction "PC5_34") (pintype "passive"))
      (node (ref "R6") (pin "2") (pinfunction "2_2") (pintype "passive"))
    )
    (net (code "23") (name "ETH_MII_RXD2") (class "Default")
      (node (ref "IC1") (pin "35") (pinfunction "PB0_35") (pintype "passive"))
      (node (ref "R7") (pin "2") (pinfunction "2_2") (pintype "passive"))
    )
    (net (code "24") (name "ETH_MII_RXD3") (class "Default")
      (node (ref "IC1") (pin "36") (pinfunction "PB1_36") (pintype "passive"))
      (node (ref "R8") (pin "2") (pinfunction "2_2") (pintype "passive"))
    )
    (net (code "25") (name "ETH_MII_RX_CLK") (class "Default")
      (node (ref "IC1") (pin "24") (pinfunction "PA1_24") (pintype "passive"))
      (node (ref "R9") (pin "2") (pinfunction "2_2") (pintype "passive"))
    )
    (net (code "26") (name "ETH_MII_RX_DV") (class "Default")
      (node (ref "IC1") (pin "32") (pinfunction "PA7_32") (pintype "passive"))
      (node (ref "R11") (pin "2") (pinfunction "2_2") (pintype "passive"))
    )
    (net (code "27") (name "ETH_MII_RX_ER") (class "Default")
      (node (ref "IC1") (pin "47") (pinfunction "PB10_47") (pintype "passive"))
      (node (ref "R10") (pin "2") (pinfunction "2_2") (pintype "passive"))
    )
    (net (code "28") (name "ETH_MII_TXD0") (class "Default")
      (node (ref "IC1") (pin "51") (pinfunction "PB12_51") (pintype "passive"))
      (node (ref "IC2") (pin "35") (pinfunction "TXD0_35") (pintype "passive"))
    )
    (net (code "29") (name "ETH_MII_TXD1") (class "Default")
      (node (ref "IC1") (pin "52") (pinfunction "PB13_52") (pintype "passive"))
      (node (ref "IC2") (pin "36") (pinfunction "TXD1_36") (pintype "passive"))
    )
    (net (code "30") (name "ETH_MII_TXD2") (class "Default")
      (node (ref "IC1") (pin "17") (pinfunction "PC2_17") (pintype "passive"))
      (node (ref "IC2") (pin "38") (pinfunction "TXD2_38") (pintype "passive"))
    )
    (net (code "31") (name "ETH_MII_TXD3") (class "Default")
      (node (ref "IC1") (pin "1") (pinfunction "PE2_1") (pintype "passive"))
      (node (ref "IC2") (pin "39") (pinfunction "TXD3_39") (pintype "passive"))
    )
    (net (code "32") (name "ETH_MII_TX_CLK") (class "Default")
      (node (ref "IC1") (pin "18") (pinfunction "PC3_18") (pintype "passive"))
      (node (ref "R4") (pin "2") (pinfunction "2_2") (pintype "passive"))
    )
    (net (code "33") (name "ETH_MII_TX_EN") (class "Default")
      (node (ref "IC1") (pin "48") (pinfunction "PB11_48") (pintype "passive"))
      (node (ref "IC2") (pin "34") (pinfunction "TXEN_34") (pintype "passive"))
    )
    (net (code "34") (name "ETH_RST") (class "Default")
      (node (ref "C11") (pin "1") (pinfunction "1_1") (pintype "passive"))
      (node (ref "IC1") (pin "64") (pinfunction "PC7_64") (pintype "passive"))
      (node (ref "IC2") (pin "47") (pinfunction "#RST_47") (pintype "passive"))
      (node (ref "R15") (pin "1") (pinfunction "1_1") (pintype "passive"))
    )
    (net (code "35") (name "EXTSUPPLY") (class "Default")
      (node (ref "C29") (pin "+") (pinfunction "+_+") (pintype "passive"))
      (node (ref "C30") (pin "+") (pinfunction "+_+") (pintype "passive"))
      (node (ref "C38") (pin "+") (pinfunction "+_+") (pintype "passive"))
      (node (ref "JP2") (pin "4") (pinfunction "4_4") (pintype "passive"))
      (node (ref "JP4") (pin "4") (pinfunction "4_4") (pintype "passive"))
      (node (ref "K2") (pin "A") (pinfunction "A_A") (pintype "passive"))
      (node (ref "U3") (pin "7") (pinfunction "VIN_7") (pintype "power_in"))
      (node (ref "U4") (pin "7") (pinfunction "VIN_7") (pintype "power_in"))
    )
    (net (code "36") (name "GND") (class "Default")
      (node (ref "C1") (pin "2") (pinfunction "2_2") (pintype "passive"))
      (node (ref "C10") (pin "-") (pinfunction "-_-") (pintype "passive"))
      (node (ref "C11") (pin "2") (pinfunction "2_2") (pintype "passive"))
      (node (ref "C12") (pin "2") (pinfunction "2_2") (pintype "passive"))
      (node (ref "C13") (pin "2") (pinfunction "2_2") (pintype "passive"))
      (node (ref "C14") (pin "-") (pinfunction "-_-") (pintype "passive"))
      (node (ref "C15") (pin "2") (pinfunction "2_2") (pintype "passive"))
      (node (ref "C16") (pin "-") (pinfunction "-_-") (pintype "passive"))
      (node (ref "C17") (pin "1") (pinfunction "1_1") (pintype "passive"))
      (node (ref "C18") (pin "1") (pinfunction "1_1") (pintype "passive"))
      (node (ref "C2") (pin "2") (pinfunction "2_2") (pintype "passive"))
      (node (ref "C20") (pin "2") (pinfunction "2_2") (pintype "passive"))
      (node (ref "C21") (pin "2") (pinfunction "2_2") (pintype "passive"))
      (node (ref "C22") (pin "2") (pinfunction "2_2") (pintype "passive"))
      (node (ref "C23") (pin "-") (pinfunction "-_-") (pintype "passive"))
      (node (ref "C24") (pin "2") (pinfunction "2_2") (pintype "passive"))
      (node (ref "C25") (pin "2") (pinfunction "2_2") (pintype "passive"))
      (node (ref "C26") (pin "2") (pinfunction "2_2") (pintype "passive"))
      (node (ref "C27") (pin "-") (pinfunction "-_-") (pintype "passive"))
      (node (ref "C28") (pin "-") (pinfunction "-_-") (pintype "passive"))
      (node (ref "C29") (pin "-") (pinfunction "-_-") (pintype "passive"))
      (node (ref "C3") (pin "2") (pinfunction "2_2") (pintype "passive"))
      (node (ref "C30") (pin "-") (pinfunction "-_-") (pintype "passive"))
      (node (ref "C31") (pin "-") (pinfunction "-_-") (pintype "passive"))
      (node (ref "C32") (pin "2") (pinfunction "2_2") (pintype "passive"))
      (node (ref "C33") (pin "2") (pinfunction "2_2") (pintype "passive"))
      (node (ref "C34") (pin "2") (pinfunction "2_2") (pintype "passive"))
      (node (ref "C35") (pin "1") (pinfunction "1_1") (pintype "passive"))
      (node (ref "C36") (pin "-") (pinfunction "-_-") (pintype "passive"))
      (node (ref "C37") (pin "1") (pinfunction "1_1") (pintype "passive"))
      (node (ref "C38") (pin "-") (pinfunction "-_-") (pintype "passive"))
      (node (ref "C39") (pin "2") (pinfunction "2_2") (pintype "passive"))
      (node (ref "C4") (pin "2") (pinfunction "2_2") (pintype "passive"))
      (node (ref "C40") (pin "2") (pinfunction "2_2") (pintype "passive"))
      (node (ref "C5") (pin "2") (pinfunction "2_2") (pintype "passive"))
      (node (ref "C6") (pin "1") (pinfunction "1_1") (pintype "passive"))
      (node (ref "C7") (pin "-") (pinfunction "-_-") (pintype "passive"))
      (node (ref "C8") (pin "-") (pinfunction "-_-") (pintype "passive"))
      (node (ref "C9") (pin "1") (pinfunction "1_1") (pintype "passive"))
      (node (ref "D1") (pin "A") (pinfunction "A_A") (pintype "passive"))
      (node (ref "D2") (pin "A") (pinfunction "A_A") (pintype "passive"))
      (node (ref "IC1") (pin "10") (pinfunction "VSS_10") (pintype "passive"))
      (node (ref "IC1") (pin "20") (pinfunction "VSSA_20") (pintype "passive"))
      (node (ref "IC1") (pin "27") (pinfunction "VSS_27") (pintype "passive"))
      (node (ref "IC1") (pin "74") (pinfunction "VSS_74") (pintype "passive"))
      (node (ref "IC1") (pin "99") (pinfunction "VSS_99") (pintype "passive"))
      (node (ref "IC2") (pin "1") (pinfunction "GND_1") (pintype "power_in"))
      (node (ref "IC2") (pin "13") (pinfunction "GND_13") (pintype "power_in"))
      (node (ref "IC2") (pin "17") (pinfunction "GND_17") (pintype "power_in"))
      (node (ref "IC2") (pin "2") (pinfunction "GND_2") (pintype "power_in"))
      (node (ref "IC2") (pin "24") (pinfunction "GND_24") (pintype "power_in"))
      (node (ref "IC2") (pin "3") (pinfunction "GND_3") (pintype "power_in"))
      (node (ref "IC2") (pin "30") (pinfunction "GND_30") (pintype "power_in"))
      (node (ref "IC2") (pin "37") (pinfunction "GND_37") (pintype "power_in"))
      (node (ref "JP1") (pin "1") (pinfunction "1_1") (pintype "passive"))
      (node (ref "JP2") (pin "1") (pinfunction "1_1") (pintype "passive"))
      (node (ref "JP4") (pin "1") (pinfunction "1_1") (pintype "passive"))
      (node (ref "JP7") (pin "3") (pinfunction "3_3") (pintype "passive"))
      (node (ref "JP8") (pin "4") (pinfunction "4_4") (pintype "passive"))
      (node (ref "K2") (pin "B") (pinfunction "B_B") (pintype "passive"))
      (node (ref "L2") (pin "1") (pinfunction "1_1") (pintype "passive"))
      (node (ref "LED1") (pin "C") (pinfunction "C_C") (pintype "passive"))
      (node (ref "LED2") (pin "C") (pinfunction "C_C") (pintype "passive"))
      (node (ref "R2") (pin "1") (pinfunction "1_1") (pintype "passive"))
      (node (ref "R20") (pin "2") (pinfunction "2_2") (pintype "passive"))
      (node (ref "R26") (pin "2") (pinfunction "2_2") (pintype "passive"))
      (node (ref "R31") (pin "2") (pinfunction "2_2") (pintype "passive"))
      (node (ref "R33") (pin "1") (pinfunction "1_1") (pintype "passive"))
      (node (ref "R35") (pin "1") (pinfunction "1_1") (pintype "passive"))
      (node (ref "R37") (pin "2") (pinfunction "2_2") (pintype "passive"))
      (node (ref "R51") (pin "2") (pinfunction "2_2") (pintype "passive"))
      (node (ref "R53") (pin "2") (pinfunction "2_2") (pintype "passive"))
      (node (ref "R57") (pin "2") (pinfunction "2_2") (pintype "passive"))
      (node (ref "R59") (pin "2") (pinfunction "2_2") (pintype "passive"))
      (node (ref "R61") (pin "2") (pinfunction "2_2") (pintype "passive"))
      (node (ref "R64") (pin "2") (pinfunction "2_2") (pintype "passive"))
      (node (ref "U1") (pin "2") (pinfunction "GND_2") (pintype "passive"))
      (node (ref "U2") (pin "2") (pinfunction "GND_2") (pintype "passive"))
      (node (ref "U3") (pin "5") (pinfunction "ON/OFF_5") (pintype "input"))
      (node (ref "U3") (pin "6") (pinfunction "GND_6") (pintype "passive"))
      (node (ref "U4") (pin "5") (pinfunction "ON/OFF_5") (pintype "input"))
      (node (ref "U4") (pin "6") (pinfunction "GND_6") (pintype "passive"))
      (node (ref "U5") (pin "11") (pinfunction "VCC-_11") (pintype "passive"))
      (node (ref "U6") (pin "4") (pinfunction "VSS_4") (pintype "power_in"))
    )
    (net (code "37") (name "JTG-TCK{slash}SWCLK") (class "Default")
      (node (ref "IC1") (pin "76") (pinfunction "PA14_76") (pintype "passive"))
      (node (ref "JP7") (pin "2") (pinfunction "2_2") (pintype "passive"))
      (node (ref "R37") (pin "1") (pinfunction "1_1") (pintype "passive"))
    )
    (net (code "38") (name "JTG-TDI") (class "Default")
      (node (ref "IC1") (pin "77") (pinfunction "PA15_77") (pintype "passive"))
    )
    (net (code "39") (name "JTG-TDO{slash}SWO") (class "Default")
      (node (ref "IC1") (pin "89") (pinfunction "PB3_89") (pintype "passive"))
      (node (ref "JP7") (pin "6") (pinfunction "6_6") (pintype "passive"))
      (node (ref "R41") (pin "2") (pinfunction "2_2") (pintype "passive"))
    )
    (net (code "40") (name "JTG-TMS{slash}SWDIO") (class "Default")
      (node (ref "IC1") (pin "72") (pinfunction "PA13_72") (pintype "passive"))
      (node (ref "JP7") (pin "4") (pinfunction "4_4") (pintype "passive"))
      (node (ref "R38") (pin "2") (pinfunction "2_2") (pintype "passive"))
    )
    (net (code "41") (name "JTG-TRST") (class "Default")
      (node (ref "IC1") (pin "90") (pinfunction "PB4_90") (pintype "passive"))
    )
    (net (code "42") (name "LED_CAN1") (class "Default")
      (node (ref "IC1") (pin "55") (pinfunction "PD8_55") (pintype "passive"))
      (node (ref "LED3") (pin "K") (pinfunction "C_K") (pintype "passive"))
    )
    (net (code "43") (name "LED_CAN2") (class "Default")
      (node (ref "IC1") (pin "56") (pinfunction "PD9_56") (pintype "passive"))
      (node (ref "LED4") (pin "K") (pinfunction "C_K") (pintype "passive"))
    )
    (net (code "44") (name "LED_GLOBAL") (class "Default")
      (node (ref "IC1") (pin "57") (pinfunction "PD10_57") (pintype "passive"))
      (node (ref "LED5") (pin "K") (pinfunction "C_K") (pintype "passive"))
    )
    (net (code "45") (name "NRST") (class "Default")
      (node (ref "C24") (pin "1") (pinfunction "1_1") (pintype "passive"))
      (node (ref "IC1") (pin "14") (pinfunction "NRST_14") (pintype "passive"))
      (node (ref "JP7") (pin "5") (pinfunction "5_5") (pintype "passive"))
      (node (ref "R3") (pin "1") (pinfunction "1_1") (pintype "passive"))
    )
    (net (code "46") (name "Net-(C5-Pad1)") (class "Default")
      (node (ref "C5") (pin "1") (pinfunction "1_1") (pintype "passive"))
      (node (ref "IC1") (pin "28") (pinfunction "VDD_28") (pintype "passive"))
    )
    (net (code "47") (name "Net-(C12-Pad1)") (class "Default")
      (node (ref "C12") (pin "1") (pinfunction "1_1") (pintype "passive"))
      (node (ref "C13") (pin "1") (pinfunction "1_1") (pintype "passive"))
      (node (ref "C14") (pin "+") (pinfunction "+_+") (pintype "passive"))
      (node (ref "IC2") (pin "31") (pinfunction "VDD_1.2_31") (pintype "passive"))
      (node (ref "IC2") (pin "4") (pinfunction "VDD_1.2_4") (pintype "passive"))
    )
    (net (code "48") (name "Net-(C17-Pad2)") (class "Default")
      (node (ref "C17") (pin "2") (pinfunction "2_2") (pintype "passive"))
      (node (ref "K1") (pin "6") (pinfunction "6_6") (pintype "passive"))
    )
    (net (code "49") (name "Net-(C18-Pad2)") (class "Default")
      (node (ref "C18") (pin "2") (pinfunction "2_2") (pintype "passive"))
      (node (ref "K1") (pin "3") (pinfunction "3_3") (pintype "passive"))
    )
    (net (code "50") (name "Net-(C19-Pad1)") (class "Default")
      (node (ref "C19") (pin "1") (pinfunction "1_1") (pintype "passive"))
      (node (ref "R16") (pin "2") (pinfunction "2_2") (pintype "passive"))
      (node (ref "R17") (pin "2") (pinfunction "2_2") (pintype "passive"))
      (node (ref "R18") (pin "2") (pinfunction "2_2") (pintype "passive"))
      (node (ref "R19") (pin "2") (pinfunction "2_2") (pintype "passive"))
    )
    (net (code "51") (name "Net-(C19-Pad2)") (class "Default")
      (node (ref "C19") (pin "2") (pinfunction "2_2") (pintype "passive"))
      (node (ref "K1") (pin "SH1") (pinfunction "SH1_SH1") (pintype "passive"))
      (node (ref "K1") (pin "SH2") (pinfunction "SH1_SH2") (pintype "passive"))
      (node (ref "L2") (pin "2") (pinfunction "2_2") (pintype "passive"))
    )
    (net (code "52") (name "Net-(IC1-BOOT0)") (class "Default")
      (node (ref "IC1") (pin "94") (pinfunction "BOOT0_94") (pintype "passive"))
      (node (ref "JP1") (pin "2") (pinfunction "2_2") (pintype "passive"))
    )
    (net (code "53") (name "Net-(IC1-PB2)") (class "Default")
      (node (ref "IC1") (pin "37") (pinfunction "PB2_37") (pintype "passive"))
      (node (ref "R1") (pin "2") (pinfunction "2_2") (pintype "passive"))
      (node (ref "R2") (pin "2") (pinfunction "2_2") (pintype "passive"))
    )
    (net (code "54") (name "Net-(IC1-VCAP_1)") (class "Default")
      (node (ref "C7") (pin "+") (pinfunction "+_+") (pintype "passive"))
      (node (ref "IC1") (pin "49") (pinfunction "VCAP_1_49") (pintype "passive"))
    )
    (net (code "55") (name "Net-(IC1-VCAP_2)") (class "Default")
      (node (ref "C8") (pin "+") (pinfunction "+_+") (pintype "passive"))
      (node (ref "IC1") (pin "73") (pinfunction "VCAP_2_73") (pintype "passive"))
    )
    (net (code "56") (name "Net-(IC2-COL{slash}CONFIG0)") (class "Default")
      (node (ref "IC2") (pin "40") (pinfunction "COL/CONFIG0_40") (pintype "passive"))
      (node (ref "R13") (pin "1") (pinfunction "1_1") (pintype "passive"))
    )
    (net (code "57") (name "Net-(IC2-CRS{slash}CONFIG1)") (class "Default")
      (node (ref "IC2") (pin "41") (pinfunction "CRS/CONFIG1_41") (pintype "passive"))
      (node (ref "R12") (pin "1") (pinfunction "1_1") (pintype "passive"))
    )
    (net (code "58") (name "Net-(IC2-NWAYEN{slash}LED0)") (class "Default")
      (node (ref "IC2") (pin "42") (pinfunction "NWAYEN/LED0_42") (pintype "passive"))
      (node (ref "K1") (pin "K_G") (pinfunction "K_K_G") (pintype "passive"))
    )
    (net (code "59") (name "Net-(IC2-REXT)") (class "Default")
      (node (ref "IC2") (pin "16") (pinfunction "REXT_16") (pintype "passive"))
      (node (ref "R20") (pin "1") (pinfunction "1_1") (pintype "passive"))
    )
    (net (code "60") (name "Net-(IC2-RXC{slash}BCASTOFF)") (class "Default")
      (node (ref "IC2") (pin "28") (pinfunction "RXC/BCASTOFF_28") (pintype "passive"))
      (node (ref "R9") (pin "1") (pinfunction "1_1") (pintype "passive"))
    )
    (net (code "61") (name "Net-(IC2-RXD0{slash}DUPLEX)") (class "Default")
      (node (ref "IC2") (pin "23") (pinfunction "RXD0/DUPLEX_23") (pintype "passive"))
      (node (ref "R5") (pin "1") (pinfunction "1_1") (pintype "passive"))
    )
    (net (code "62") (name "Net-(IC2-RXD1{slash}PHYAD2)") (class "Default")
      (node (ref "IC2") (pin "22") (pinfunction "RXD1/PHYAD2_22") (pintype "passive"))
      (node (ref "R6") (pin "1") (pinfunction "1_1") (pintype "passive"))
    )
    (net (code "63") (name "Net-(IC2-RXD2{slash}PHYAD1)") (class "Default")
      (node (ref "IC2") (pin "21") (pinfunction "RXD2/PHYAD1_21") (pintype "passive"))
      (node (ref "R7") (pin "1") (pinfunction "1_1") (pintype "passive"))
    )
    (net (code "64") (name "Net-(IC2-RXD3{slash}PHYAD0)") (class "Default")
      (node (ref "IC2") (pin "20") (pinfunction "RXD3/PHYAD0_20") (pintype "passive"))
      (node (ref "R8") (pin "1") (pinfunction "1_1") (pintype "passive"))
    )
    (net (code "65") (name "Net-(IC2-RXDV{slash}CONFIG2)") (class "Default")
      (node (ref "IC2") (pin "27") (pinfunction "RXDV/CONFIG2_27") (pintype "passive"))
      (node (ref "R11") (pin "1") (pinfunction "1_1") (pintype "passive"))
    )
    (net (code "66") (name "Net-(IC2-RXER{slash}ISO)") (class "Default")
      (node (ref "IC2") (pin "29") (pinfunction "RXER/ISO_29") (pintype "passive"))
      (node (ref "R10") (pin "1") (pinfunction "1_1") (pintype "passive"))
    )
    (net (code "67") (name "Net-(IC2-RXM)") (class "Default")
      (node (ref "IC2") (pin "9") (pinfunction "RXM_9") (pintype "passive"))
      (node (ref "K1") (pin "8") (pinfunction "8_8") (pintype "passive"))
    )
    (net (code "68") (name "Net-(IC2-RXP)") (class "Default")
      (node (ref "IC2") (pin "10") (pinfunction "RXP_10") (pintype "passive"))
      (node (ref "K1") (pin "7") (pinfunction "7_7") (pintype "passive"))
    )
    (net (code "69") (name "Net-(IC2-SPEED{slash}LED1)") (class "Default")
      (node (ref "IC2") (pin "43") (pinfunction "SPEED/LED1_43") (pintype "passive"))
      (node (ref "K1") (pin "K_Y") (pinfunction "K_K_Y") (pintype "passive"))
    )
    (net (code "70") (name "Net-(IC2-TXC)") (class "Default")
      (node (ref "IC2") (pin "33") (pinfunction "TXC_33") (pintype "passive"))
      (node (ref "R4") (pin "1") (pinfunction "1_1") (pintype "passive"))
    )
    (net (code "71") (name "Net-(IC2-TXM)") (class "Default")
      (node (ref "IC2") (pin "11") (pinfunction "TXM_11") (pintype "passive"))
      (node (ref "K1") (pin "2") (pinfunction "2_2") (pintype "passive"))
    )
    (net (code "72") (name "Net-(IC2-TXP)") (class "Default")
      (node (ref "IC2") (pin "12") (pinfunction "TXP_12") (pintype "passive"))
      (node (ref "K1") (pin "1") (pinfunction "1_1") (pintype "passive"))
    )
    (net (code "73") (name "Net-(IC2-VDDA_3.3)") (class "Default")
      (node (ref "C22") (pin "1") (pinfunction "1_1") (pintype "passive"))
      (node (ref "C23") (pin "+") (pinfunction "+_+") (pintype "passive"))
      (node (ref "IC2") (pin "7") (pinfunction "VDDA_3.3_7") (pintype "passive"))
      (node (ref "L1") (pin "1") (pinfunction "1_1") (pintype "passive"))
    )
    (net (code "74") (name "Net-(IC2-XI)") (class "Default")
      (node (ref "C20") (pin "1") (pinfunction "1_1") (pintype "passive"))
      (node (ref "IC2") (pin "15") (pinfunction "XI_15") (pintype "passive"))
      (node (ref "Q1") (pin "1") (pinfunction "1_1") (pintype "passive"))
    )
    (net (code "75") (name "Net-(IC2-XO)") (class "Default")
      (node (ref "C21") (pin "1") (pinfunction "1_1") (pintype "passive"))
      (node (ref "IC2") (pin "14") (pinfunction "XO_14") (pintype "passive"))
      (node (ref "Q1") (pin "2") (pinfunction "2_2") (pintype "passive"))
    )
    (net (code "76") (name "Net-(JP3-Pad1)") (class "Default")
      (node (ref "JP3") (pin "1") (pinfunction "1_1") (pintype "passive"))
      (node (ref "R27") (pin "2") (pinfunction "2_2") (pintype "passive"))
    )
    (net (code "77") (name "Net-(JP5-Pad1)") (class "Default")
      (node (ref "JP5") (pin "1") (pinfunction "1_1") (pintype "passive"))
      (node (ref "R32") (pin "2") (pinfunction "2_2") (pintype "passive"))
    )
    (net (code "78") (name "Net-(JP7-Pad1)") (class "Default")
      (node (ref "JP7") (pin "1") (pinfunction "1_1") (pintype "passive"))
      (node (ref "R42") (pin "2") (pinfunction "2_2") (pintype "passive"))
    )
    (net (code "79") (name "Net-(K1-Pad4)") (class "Default")
      (node (ref "K1") (pin "4") (pinfunction "4_4") (pintype "passive"))
      (node (ref "R16") (pin "1") (pinfunction "1_1") (pintype "passive"))
    )
    (net (code "80") (name "Net-(K1-Pad5)") (class "Default")
      (node (ref "K1") (pin "5") (pinfunction "5_5") (pintype "passive"))
      (node (ref "R19") (pin "1") (pinfunction "1_1") (pintype "passive"))
    )
    (net (code "81") (name "Net-(K1-Pad9)") (class "Default")
      (node (ref "K1") (pin "9") (pinfunction "9_9") (pintype "passive"))
      (node (ref "R17") (pin "1") (pinfunction "1_1") (pintype "passive"))
    )
    (net (code "82") (name "Net-(K1-Pad10)") (class "Default")
      (node (ref "K1") (pin "10") (pinfunction "10_10") (pintype "passive"))
      (node (ref "R18") (pin "1") (pinfunction "1_1") (pintype "passive"))
    )
    (net (code "83") (name "Net-(K1B-A)") (class "Default")
      (node (ref "K1") (pin "A_Y") (pinfunction "A_A_Y") (pintype "passive"))
      (node (ref "R22") (pin "2") (pinfunction "2_2") (pintype "passive"))
    )
    (net (code "84") (name "Net-(K1C-A)") (class "Default")
      (node (ref "K1") (pin "A_G") (pinfunction "A_A_G") (pintype "passive"))
      (node (ref "R21") (pin "2") (pinfunction "2_2") (pintype "passive"))
    )
    (net (code "85") (name "Net-(LED1-PadA)") (class "Default")
      (node (ref "LED1") (pin "A") (pinfunction "A_A") (pintype "passive"))
      (node (ref "R43") (pin "1") (pinfunction "1_1") (pintype "passive"))
    )
    (net (code "86") (name "Net-(LED2-PadA)") (class "Default")
      (node (ref "LED2") (pin "A") (pinfunction "A_A") (pintype "passive"))
      (node (ref "R44") (pin "1") (pinfunction "1_1") (pintype "passive"))
    )
    (net (code "87") (name "Net-(LED3-PadA)") (class "Default")
      (node (ref "LED3") (pin "A") (pinfunction "A_A") (pintype "passive"))
      (node (ref "R45") (pin "1") (pinfunction "1_1") (pintype "passive"))
    )
    (net (code "88") (name "Net-(LED4-PadA)") (class "Default")
      (node (ref "LED4") (pin "A") (pinfunction "A_A") (pintype "passive"))
      (node (ref "R46") (pin "1") (pinfunction "1_1") (pintype "passive"))
    )
    (net (code "89") (name "Net-(LED5-PadA)") (class "Default")
      (node (ref "LED5") (pin "A") (pinfunction "A_A") (pintype "passive"))
      (node (ref "R47") (pin "1") (pinfunction "1_1") (pintype "passive"))
    )
    (net (code "90") (name "Net-(U1-RS)") (class "Default")
      (node (ref "R24") (pin "2") (pinfunction "2_2") (pintype "passive"))
      (node (ref "R25") (pin "2") (pinfunction "2_2") (pintype "passive"))
      (node (ref "R26") (pin "1") (pinfunction "1_1") (pintype "passive"))
      (node (ref "U1") (pin "8") (pinfunction "RS_8") (pintype "input"))
    )
    (net (code "91") (name "Net-(U2-CANH)") (class "Default")
      (node (ref "JP4") (pin "2") (pinfunction "2_2") (pintype "passive"))
      (node (ref "JP5") (pin "2") (pinfunction "2_2") (pintype "passive"))
      (node (ref "U2") (pin "7") (pinfunction "CANH_7") (pintype "output"))
    )
    (net (code "92") (name "Net-(U2-CANL)") (class "Default")
      (node (ref "JP4") (pin "3") (pinfunction "3_3") (pintype "passive"))
      (node (ref "R32") (pin "1") (pinfunction "1_1") (pintype "passive"))
      (node (ref "U2") (pin "6") (pinfunction "CANL_6") (pintype "output"))
    )
    (net (code "93") (name "Net-(U2-RS)") (class "Default")
      (node (ref "R28") (pin "2") (pinfunction "2_2") (pintype "passive"))
      (node (ref "R29") (pin "2") (pinfunction "2_2") (pintype "passive"))
      (node (ref "R31") (pin "1") (pinfunction "1_1") (pintype "passive"))
      (node (ref "U2") (pin "8") (pinfunction "RS_8") (pintype "input"))
    )
    (net (code "94") (name "Net-(U3-FB)") (class "Default")
      (node (ref "R30") (pin "1") (pinfunction "1_1") (pintype "passive"))
      (node (ref "R33") (pin "2") (pinfunction "2_2") (pintype "passive"))
      (node (ref "U3") (pin "4") (pinfunction "FB_4") (pintype "input"))
    )
    (net (code "95") (name "Net-(U3-OUT)") (class "Default")
      (node (ref "D1") (pin "C") (pinfunction "C_C") (pintype "passive"))
      (node (ref "L3") (pin "1") (pinfunction "1_1") (pintype "passive"))
      (node (ref "U3") (pin "8") (pinfunction "OUT_8") (pintype "output"))
    )
    (net (code "96") (name "Net-(U4-FB)") (class "Default")
      (node (ref "R34") (pin "1") (pinfunction "1_1") (pintype "passive"))
      (node (ref "R35") (pin "2") (pinfunction "2_2") (pintype "passive"))
      (node (ref "U4") (pin "4") (pinfunction "FB_4") (pintype "input"))
    )
    (net (code "97") (name "Net-(U4-OUT)") (class "Default")
      (node (ref "D2") (pin "C") (pinfunction "C_C") (pintype "passive"))
      (node (ref "L4") (pin "1") (pinfunction "1_1") (pintype "passive"))
      (node (ref "U4") (pin "8") (pinfunction "OUT_8") (pintype "output"))
    )
    (net (code "98") (name "Net-(U5-NEG_1)") (class "Default")
      (node (ref "R55") (pin "1") (pinfunction "1_1") (pintype "passive"))
      (node (ref "R63") (pin "1") (pinfunction "1_1") (pintype "passive"))
      (node (ref "U5") (pin "2") (pinfunction "NEG_1_2") (pintype "input"))
      (node (ref "U5") (pin "7") (pinfunction "OUT_2_7") (pintype "output"))
    )
    (net (code "99") (name "Net-(U5-NEG_2)") (class "Default")
      (node (ref "R54") (pin "2") (pinfunction "2_2") (pintype "passive"))
      (node (ref "R55") (pin "2") (pinfunction "2_2") (pintype "passive"))
      (node (ref "U5") (pin "6") (pinfunction "NEG_2_6") (pintype "input"))
    )
    (net (code "100") (name "Net-(U5-NEG_3)") (class "Default")
      (node (ref "R50") (pin "1") (pinfunction "1_1") (pintype "passive"))
      (node (ref "R54") (pin "1") (pinfunction "1_1") (pintype "passive"))
      (node (ref "U5") (pin "8") (pinfunction "OUT_3_8") (pintype "output"))
      (node (ref "U5") (pin "9") (pinfunction "NEG_3_9") (pintype "input"))
    )
    (net (code "101") (name "Net-(U5-NEG_4)") (class "Default")
      (node (ref "R52") (pin "1") (pinfunction "1_1") (pintype "passive"))
      (node (ref "R56") (pin "1") (pinfunction "1_1") (pintype "passive"))
      (node (ref "U5") (pin "13") (pinfunction "NEG_4_13") (pintype "input"))
      (node (ref "U5") (pin "14") (pinfunction "OUT_4_14") (pintype "output"))
    )
    (net (code "102") (name "Net-(U5-OUT_1)") (class "Default")
      (node (ref "R58") (pin "1") (pinfunction "1_1") (pintype "passive"))
      (node (ref "U5") (pin "1") (pinfunction "OUT_1_1") (pintype "output"))
    )
    (net (code "103") (name "Net-(U5-POS_1)") (class "Default")
      (node (ref "R60") (pin "1") (pinfunction "1_1") (pintype "passive"))
      (node (ref "U5") (pin "3") (pinfunction "POS_1_3") (pintype "input"))
      (node (ref "U6") (pin "1") (pinfunction "VOUTA_1") (pintype "output"))
    )
    (net (code "104") (name "Net-(U5-POS_2)") (class "Default")
      (node (ref "R56") (pin "2") (pinfunction "2_2") (pintype "passive"))
      (node (ref "R57") (pin "1") (pinfunction "1_1") (pintype "passive"))
      (node (ref "U5") (pin "5") (pinfunction "POS_2_5") (pintype "input"))
    )
    (net (code "105") (name "Net-(U5-POS_3)") (class "Default")
      (node (ref "R48") (pin "1") (pinfunction "1_1") (pintype "passive"))
      (node (ref "U5") (pin "10") (pinfunction "POS_3_10") (pintype "input"))
    )
    (net (code "106") (name "Net-(U5-POS_4)") (class "Default")
      (node (ref "R49") (pin "1") (pinfunction "1_1") (pintype "passive"))
      (node (ref "U5") (pin "12") (pinfunction "POS_4_12") (pintype "input"))
    )
    (net (code "107") (name "Net-(U6-VINA+)") (class "Default")
      (node (ref "C34") (pin "1") (pinfunction "1_1") (pintype "passive"))
      (node (ref "R62") (pin "1") (pinfunction "1_1") (pintype "passive"))
      (node (ref "U6") (pin "3") (pinfunction "VINA+_3") (pintype "input"))
    )
    (net (code "108") (name "Net-(U6-VINA-)") (class "Default")
      (node (ref "R60") (pin "2") (pinfunction "2_2") (pintype "passive"))
      (node (ref "R61") (pin "1") (pinfunction "1_1") (pintype "passive"))
      (node (ref "U6") (pin "2") (pinfunction "VINA-_2") (pintype "input"))
    )
    (net (code "109") (name "OSC_IN") (class "Default")
      (node (ref "C39") (pin "1") (pinfunction "1_1") (pintype "passive"))
      (node (ref "IC1") (pin "12") (pinfunction "PH0_12") (pintype "passive"))
      (node (ref "Q2") (pin "2") (pinfunction "2_2") (pintype "passive"))
    )
    (net (code "110") (name "OSC_OUT") (class "Default")
      (node (ref "C40") (pin "1") (pinfunction "1_1") (pintype "passive"))
      (node (ref "IC1") (pin "13") (pinfunction "PH1_13") (pintype "passive"))
      (node (ref "Q2") (pin "1") (pinfunction "1_1") (pintype "passive"))
    )
    (net (code "111") (name "USART1_RX") (class "Default")
      (node (ref "IC1") (pin "69") (pinfunction "PA10_69") (pintype "passive"))
      (node (ref "JP8") (pin "3") (pinfunction "3_3") (pintype "passive"))
    )
    (net (code "112") (name "USART1_TX") (class "Default")
      (node (ref "IC1") (pin "68") (pinfunction "PA9_68") (pintype "passive"))
      (node (ref "JP8") (pin "2") (pinfunction "2_2") (pintype "passive"))
    )
    (net (code "113") (name "V+") (class "Default")
      (node (ref "C27") (pin "+") (pinfunction "+_+") (pintype "passive"))
      (node (ref "C31") (pin "+") (pinfunction "+_+") (pintype "passive"))
      (node (ref "C32") (pin "1") (pinfunction "1_1") (pintype "passive"))
      (node (ref "C33") (pin "1") (pinfunction "1_1") (pintype "passive"))
      (node (ref "L3") (pin "2") (pinfunction "2_2") (pintype "passive"))
      (node (ref "R30") (pin "2") (pinfunction "2_2") (pintype "passive"))
      (node (ref "R43") (pin "2") (pinfunction "2_2") (pintype "passive"))
      (node (ref "U5") (pin "4") (pinfunction "VCC+_4") (pintype "power_in"))
      (node (ref "U6") (pin "8") (pinfunction "VDD_8") (pintype "power_in"))
    )
    (net (code "114") (name "unconnected-(IC1-PB7-Pad93)") (class "Default")
      (node (ref "IC1") (pin "93") (pinfunction "PB7_93") (pintype "passive"))
    )
    (net (code "115") (name "unconnected-(IC1-PB8-Pad95)") (class "Default")
      (node (ref "IC1") (pin "95") (pinfunction "PB8_95") (pintype "passive"))
    )
    (net (code "116") (name "unconnected-(IC1-PB9-Pad96)") (class "Default")
      (node (ref "IC1") (pin "96") (pinfunction "PB9_96") (pintype "passive"))
    )
    (net (code "117") (name "unconnected-(IC1-PB14-Pad53)") (class "Default")
      (node (ref "IC1") (pin "53") (pinfunction "PB14_53") (pintype "passive"))
    )
    (net (code "118") (name "unconnected-(IC1-PB15-Pad54)") (class "Default")
      (node (ref "IC1") (pin "54") (pinfunction "PB15_54") (pintype "passive"))
    )
    (net (code "119") (name "unconnected-(IC1-PC10-Pad78)") (class "Default")
      (node (ref "IC1") (pin "78") (pinfunction "PC10_78") (pintype "passive"))
    )
    (net (code "120") (name "unconnected-(IC1-PC11-Pad79)") (class "Default")
      (node (ref "IC1") (pin "79") (pinfunction "PC11_79") (pintype "passive"))
    )
    (net (code "121") (name "unconnected-(IC1-PC12-Pad80)") (class "Default")
      (node (ref "IC1") (pin "80") (pinfunction "PC12_80") (pintype "passive"))
    )
    (net (code "122") (name "unconnected-(IC1-PC13-Pad7)") (class "Default")
      (node (ref "IC1") (pin "7") (pinfunction "PC13_7") (pintype "passive"))
    )
    (net (code "123") (name "unconnected-(IC1-PC14-Pad8)") (class "Default")
      (node (ref "IC1") (pin "8") (pinfunction "PC14_8") (pintype "passive"))
    )
    (net (code "124") (name "unconnected-(IC1-PC15-Pad9)") (class "Default")
      (node (ref "IC1") (pin "9") (pinfunction "PC15_9") (pintype "passive"))
    )
    (net (code "125") (name "unconnected-(IC1-PD0-Pad81)") (class "Default")
      (node (ref "IC1") (pin "81") (pinfunction "PD0_81") (pintype "passive"))
    )
    (net (code "126") (name "unconnected-(IC1-PD1-Pad82)") (class "Default")
      (node (ref "IC1") (pin "82") (pinfunction "PD1_82") (pintype "passive"))
    )
    (net (code "127") (name "unconnected-(IC1-PD2-Pad83)") (class "Default")
      (node (ref "IC1") (pin "83") (pinfunction "PD2_83") (pintype "passive"))
    )
    (net (code "128") (name "unconnected-(IC1-PD3-Pad84)") (class "Default")
      (node (ref "IC1") (pin "84") (pinfunction "PD3_84") (pintype "passive"))
    )
    (net (code "129") (name "unconnected-(IC1-PD4-Pad85)") (class "Default")
      (node (ref "IC1") (pin "85") (pinfunction "PD4_85") (pintype "passive"))
    )
    (net (code "130") (name "unconnected-(IC1-PD5-Pad86)") (class "Default")
      (node (ref "IC1") (pin "86") (pinfunction "PD5_86") (pintype "passive"))
    )
    (net (code "131") (name "unconnected-(IC1-PD6-Pad87)") (class "Default")
      (node (ref "IC1") (pin "87") (pinfunction "PD6_87") (pintype "passive"))
    )
    (net (code "132") (name "unconnected-(IC1-PD7-Pad88)") (class "Default")
      (node (ref "IC1") (pin "88") (pinfunction "PD7_88") (pintype "passive"))
    )
    (net (code "133") (name "unconnected-(IC1-PD11-Pad58)") (class "Default")
      (node (ref "IC1") (pin "58") (pinfunction "PD11_58") (pintype "passive"))
    )
    (net (code "134") (name "unconnected-(IC1-PD13-Pad60)") (class "Default")
      (node (ref "IC1") (pin "60") (pinfunction "PD13_60") (pintype "passive"))
    )
    (net (code "135") (name "unconnected-(IC1-PD14-Pad61)") (class "Default")
      (node (ref "IC1") (pin "61") (pinfunction "PD14_61") (pintype "passive"))
    )
    (net (code "136") (name "unconnected-(IC1-PD15-Pad62)") (class "Default")
      (node (ref "IC1") (pin "62") (pinfunction "PD15_62") (pintype "passive"))
    )
    (net (code "137") (name "unconnected-(IC1-PE0-Pad97)") (class "Default")
      (node (ref "IC1") (pin "97") (pinfunction "PE0_97") (pintype "passive"))
    )
    (net (code "138") (name "unconnected-(IC1-PE1-Pad98)") (class "Default")
      (node (ref "IC1") (pin "98") (pinfunction "PE1_98") (pintype "passive"))
    )
    (net (code "139") (name "unconnected-(IC1-PE3-Pad2)") (class "Default")
      (node (ref "IC1") (pin "2") (pinfunction "PE3_2") (pintype "passive"))
    )
    (net (code "140") (name "unconnected-(IC1-PE4-Pad3)") (class "Default")
      (node (ref "IC1") (pin "3") (pinfunction "PE4_3") (pintype "passive"))
    )
    (net (code "141") (name "unconnected-(IC1-PE5-Pad4)") (class "Default")
      (node (ref "IC1") (pin "4") (pinfunction "PE5_4") (pintype "passive"))
    )
    (net (code "142") (name "unconnected-(IC1-PE6-Pad5)") (class "Default")
      (node (ref "IC1") (pin "5") (pinfunction "PE6_5") (pintype "passive"))
    )
    (net (code "143") (name "unconnected-(IC1-PE7-Pad38)") (class "Default")
      (node (ref "IC1") (pin "38") (pinfunction "PE7_38") (pintype "passive"))
    )
    (net (code "144") (name "unconnected-(IC1-PE8-Pad39)") (class "Default")
      (node (ref "IC1") (pin "39") (pinfunction "PE8_39") (pintype "passive"))
    )
    (net (code "145") (name "unconnected-(IC1-PE10-Pad41)") (class "Default")
      (node (ref "IC1") (pin "41") (pinfunction "PE10_41") (pintype "passive"))
    )
    (net (code "146") (name "unconnected-(IC1-PE12-Pad43)") (class "Default")
      (node (ref "IC1") (pin "43") (pinfunction "PE12_43") (pintype "passive"))
    )
    (net (code "147") (name "unconnected-(IC1-PE13-Pad44)") (class "Default")
      (node (ref "IC1") (pin "44") (pinfunction "PE13_44") (pintype "passive"))
    )
    (net (code "148") (name "unconnected-(IC1-PE14-Pad45)") (class "Default")
      (node (ref "IC1") (pin "45") (pinfunction "PE14_45") (pintype "passive"))
    )
    (net (code "149") (name "unconnected-(IC1-PE15-Pad46)") (class "Default")
      (node (ref "IC1") (pin "46") (pinfunction "PE15_46") (pintype "passive"))
    )
    (net (code "150") (name "unconnected-(K2-PadBK)") (class "Default")
      (node (ref "K2") (pin "BK") (pinfunction "BK_BK") (pintype "passive"))
    )
    (net (code "151") (name "unconnected-(U1-VREF-Pad5)") (class "Default")
      (node (ref "U1") (pin "5") (pinfunction "VREF_5") (pintype "output"))
    )
    (net (code "152") (name "unconnected-(U2-VREF-Pad5)") (class "Default")
      (node (ref "U2") (pin "5") (pinfunction "VREF_5") (pintype "output"))
    )
    (net (code "153") (name "unconnected-(U3-NC-Pad3)") (class "Default")
      (node (ref "U3") (pin "3") (pinfunction "NC_3") (pintype "no_connect"))
    )
    (net (code "154") (name "unconnected-(U3-NC_2-Pad1)") (class "Default")
      (node (ref "U3") (pin "1") (pinfunction "NC_2_1") (pintype "no_connect"))
    )
    (net (code "155") (name "unconnected-(U3-NC_3-Pad2)") (class "Default")
      (node (ref "U3") (pin "2") (pinfunction "NC_3_2") (pintype "no_connect"))
    )
    (net (code "156") (name "unconnected-(U4-NC-Pad3)") (class "Default")
      (node (ref "U4") (pin "3") (pinfunction "NC_3") (pintype "no_connect"))
    )
    (net (code "157") (name "unconnected-(U4-NC_2-Pad1)") (class "Default")
      (node (ref "U4") (pin "1") (pinfunction "NC_2_1") (pintype "no_connect"))
    )
    (net (code "158") (name "unconnected-(U4-NC_3-Pad2)") (class "Default")
      (node (ref "U4") (pin "2") (pinfunction "NC_3_2") (pintype "no_connect"))
    )
    (net (code "159") (name "unconnected-(U6-VINB+-Pad5)") (class "Default")
      (node (ref "U6") (pin "5") (pinfunction "VINB+_5") (pintype "input"))
    )
    (net (code "160") (name "unconnected-(U6-VINB--Pad6)") (class "Default")
      (node (ref "U6") (pin "6") (pinfunction "VINB-_6") (pintype "input"))
    )
    (net (code "161") (name "unconnected-(U6-VOUTB-Pad7)") (class "Default")
      (node (ref "U6") (pin "7") (pinfunction "VOUTB_7") (pintype "output"))
    )
  )
)
